# Titan_v1p4.net
KiCad netlist of a schematic drawn in EAGLE
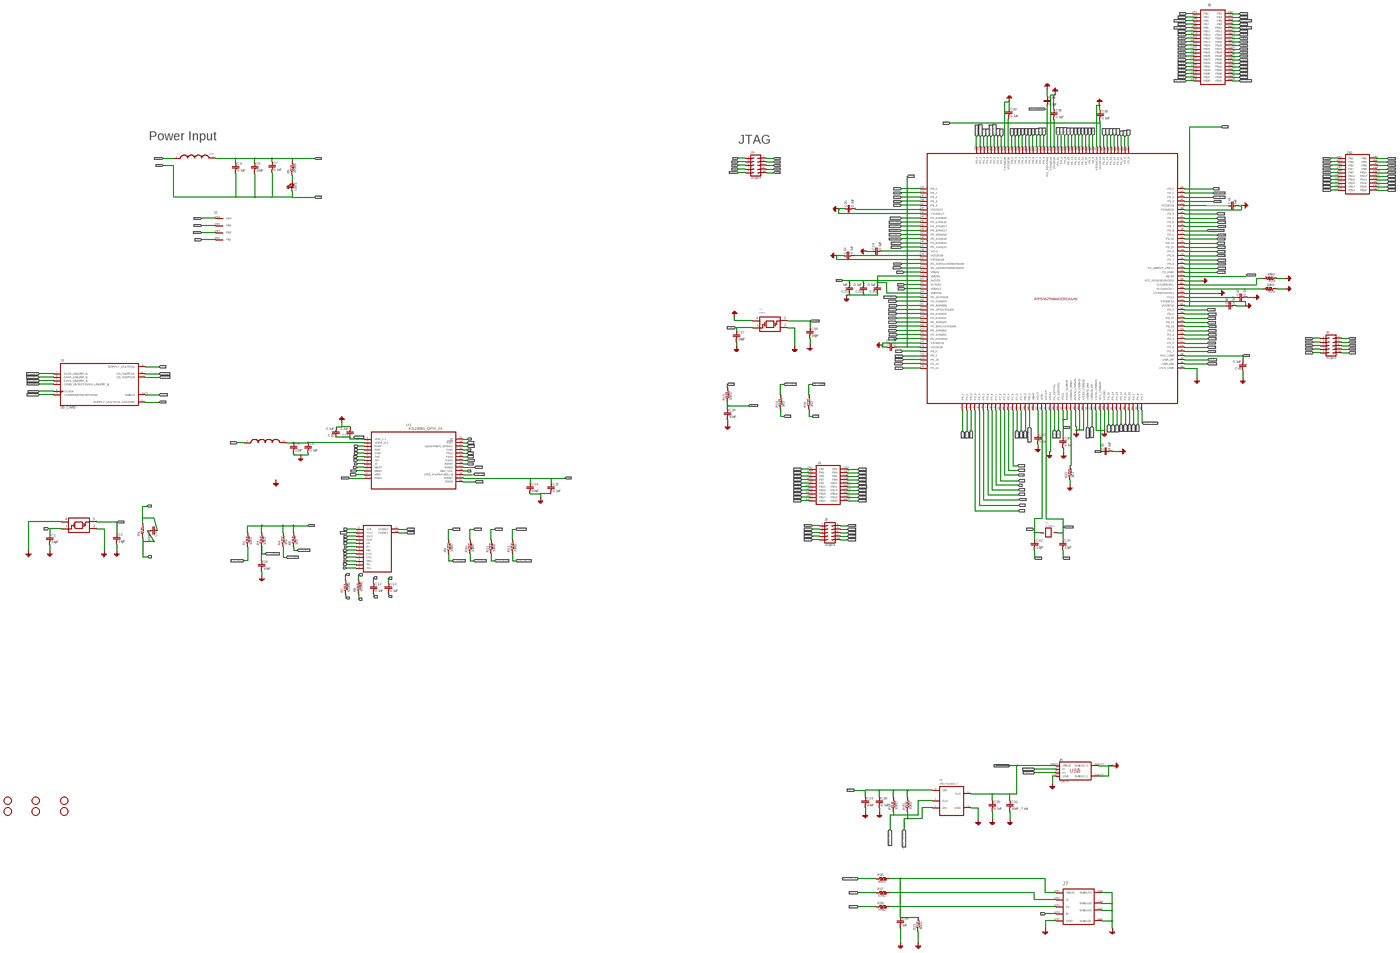
[diagram p0: schematic, sheet 1, overview]
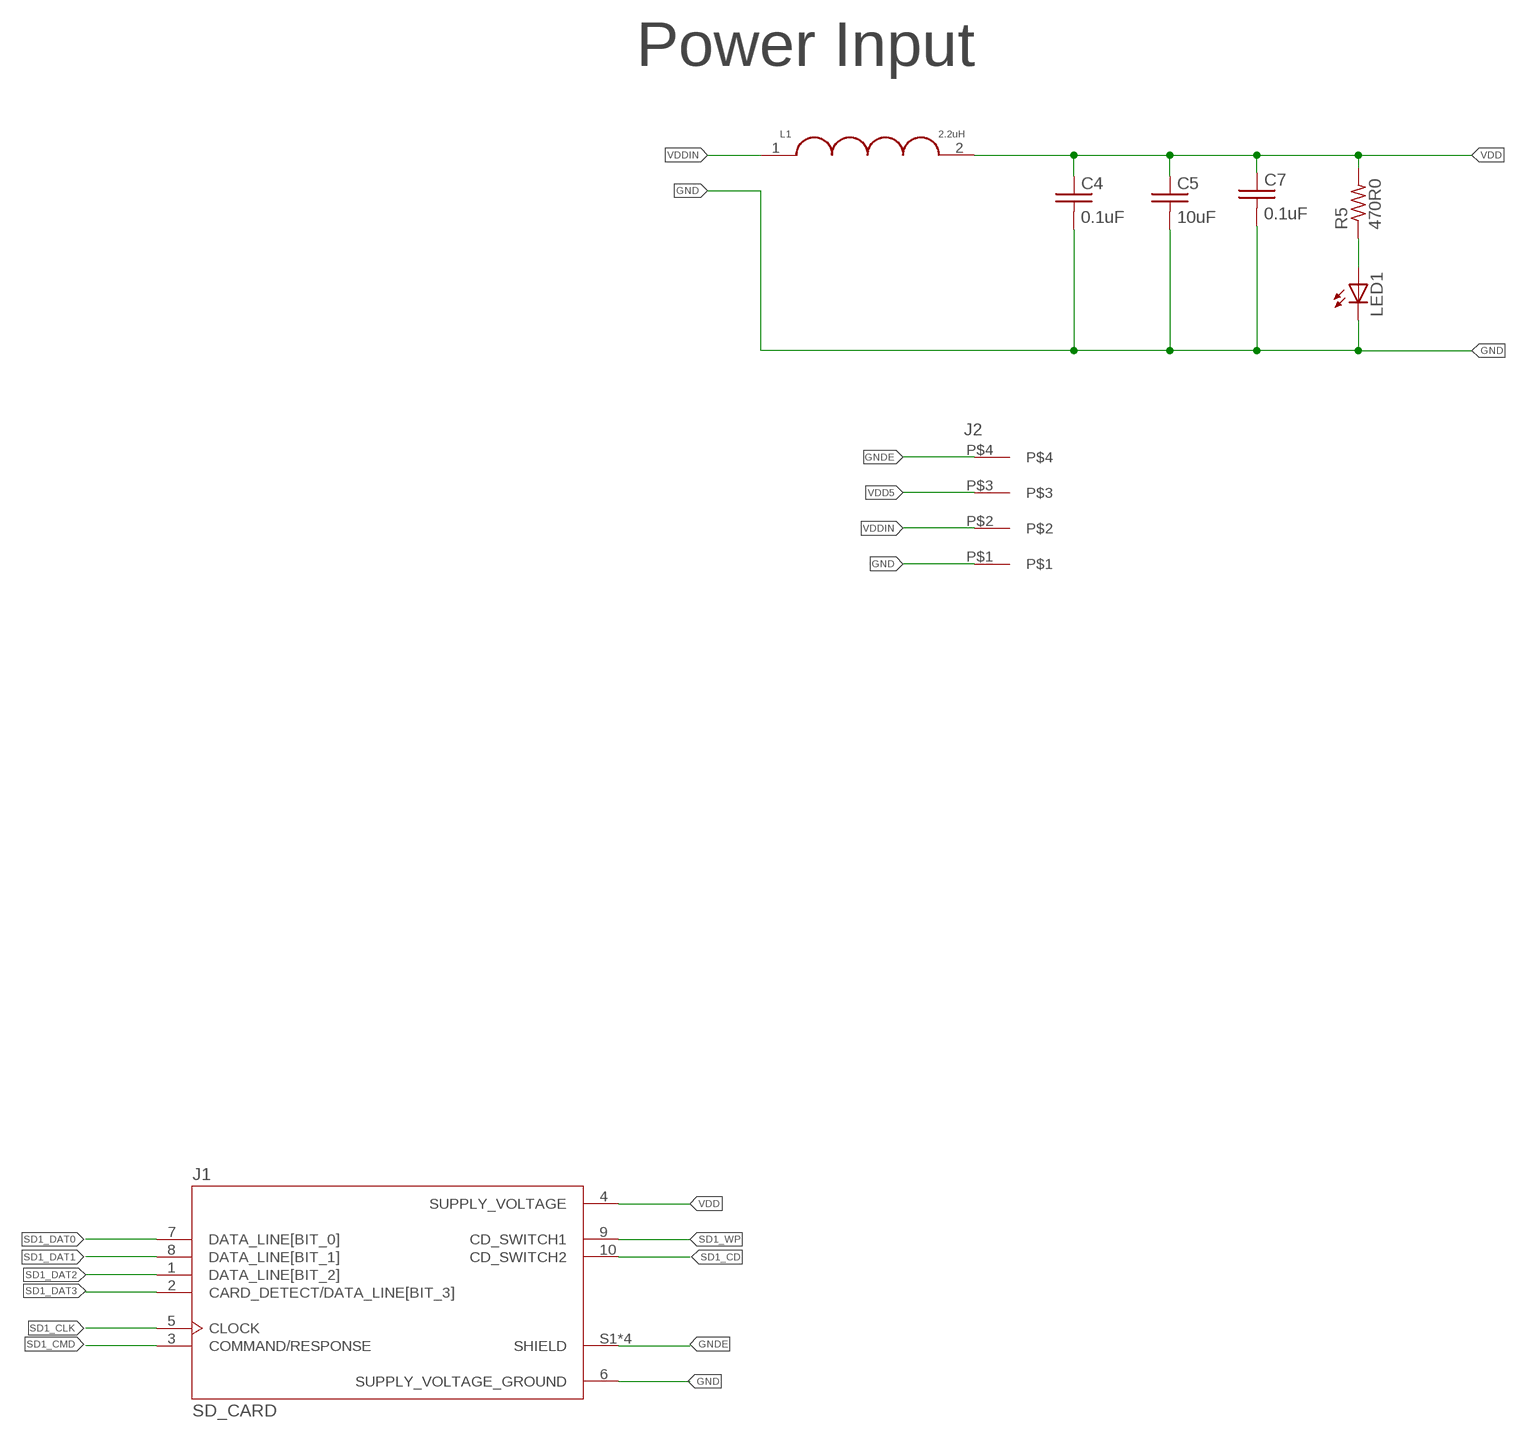
[diagram p1: schematic, sheet 1, part 1 of 5]
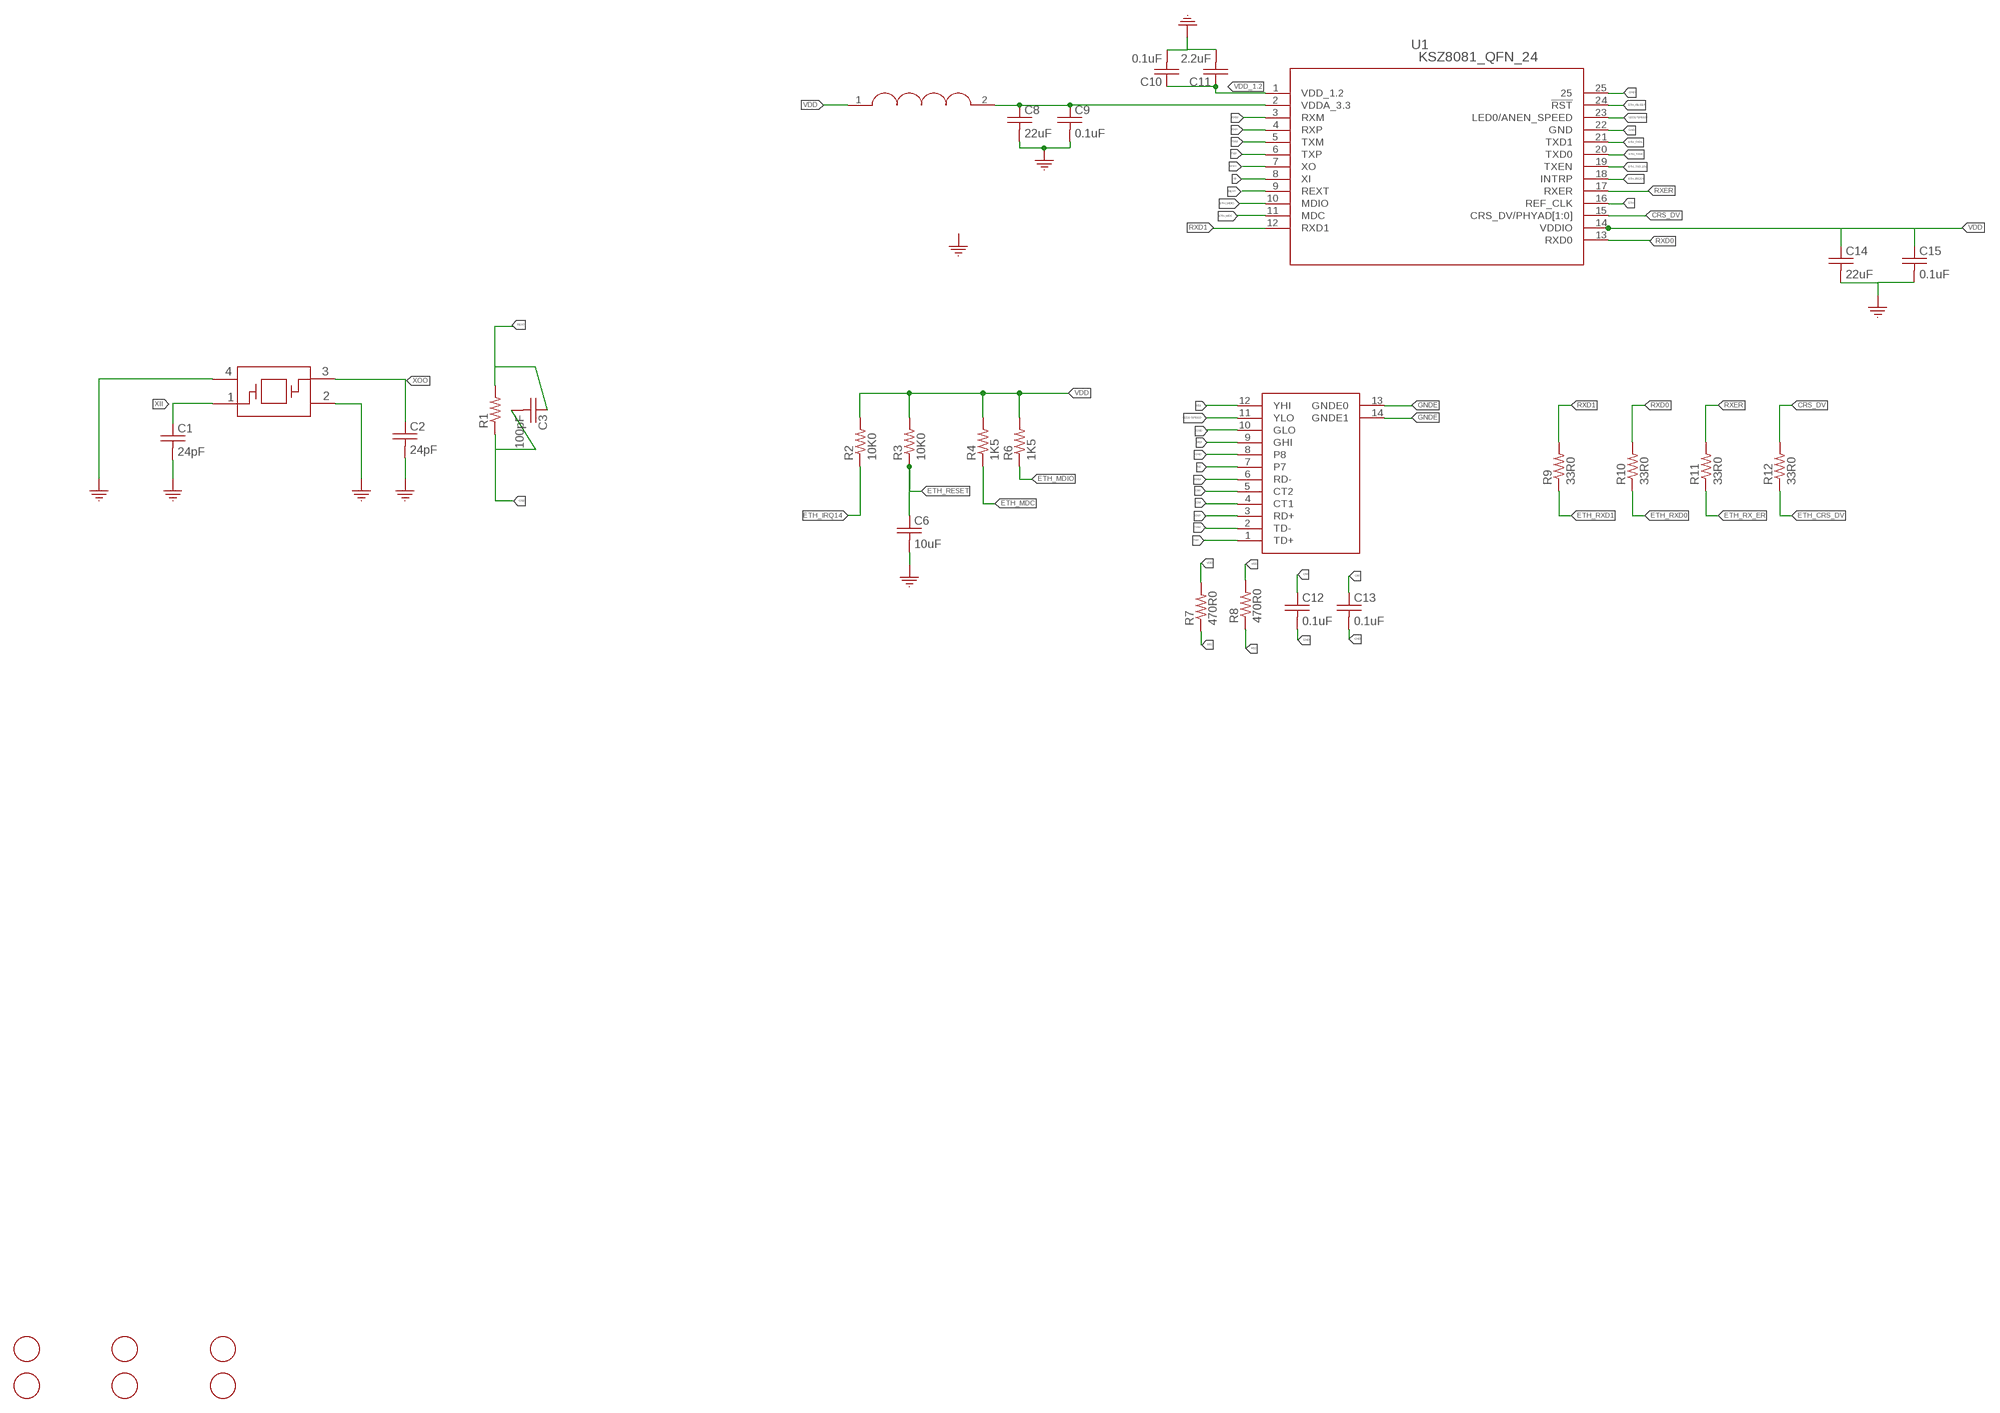
[diagram p2: schematic, sheet 1, part 2 of 5]
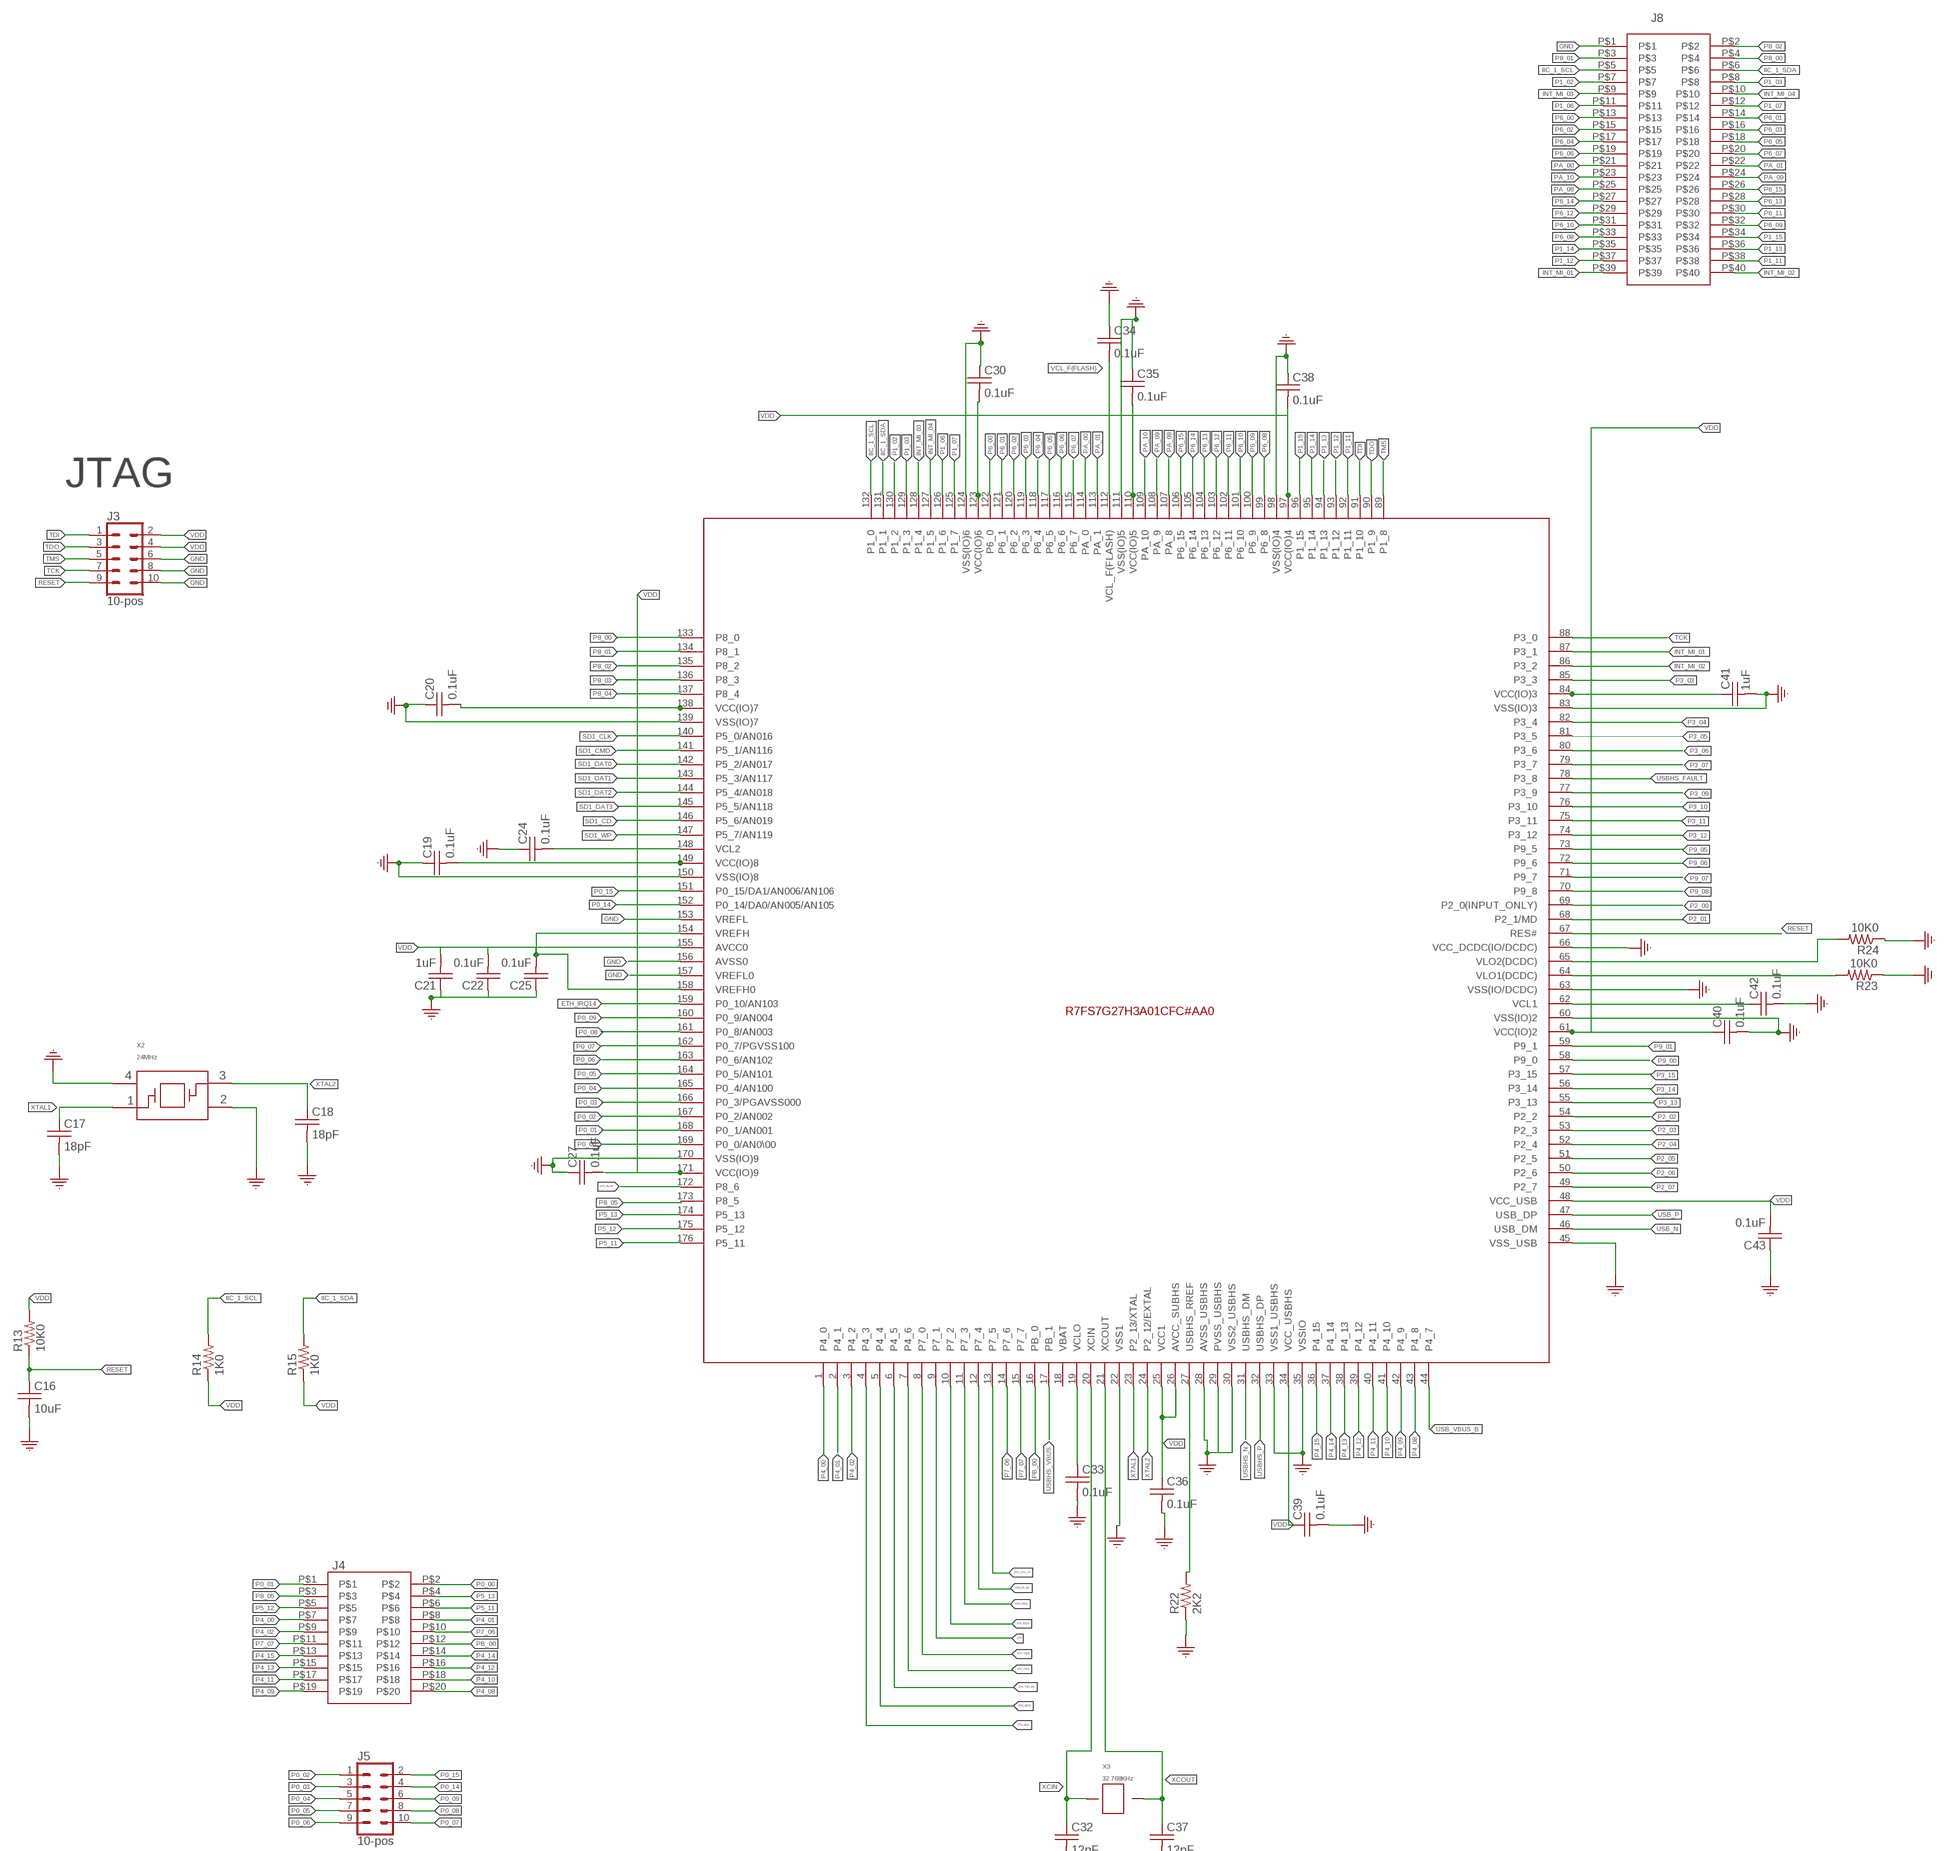
[diagram p3: schematic, sheet 1, part 3 of 5]
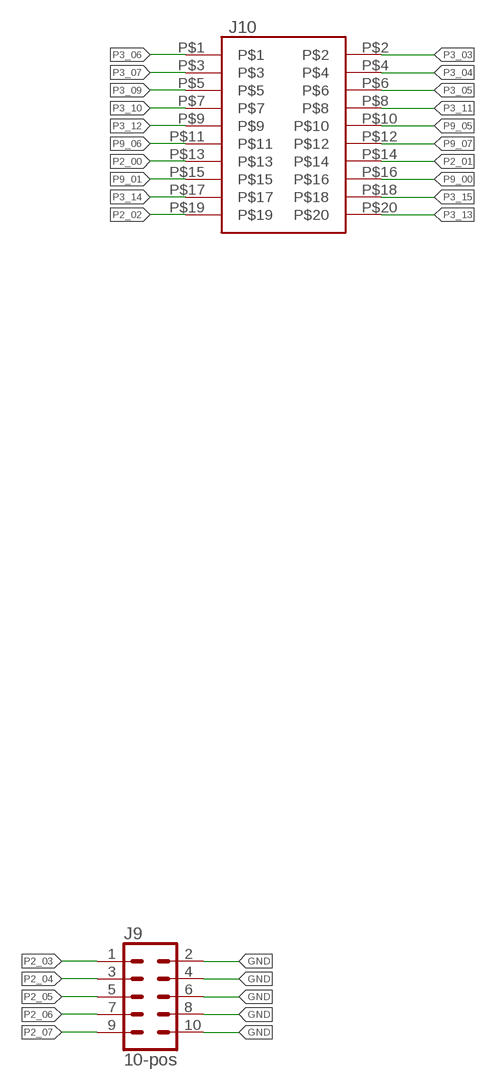
[diagram p4: schematic, sheet 1, part 4 of 5]
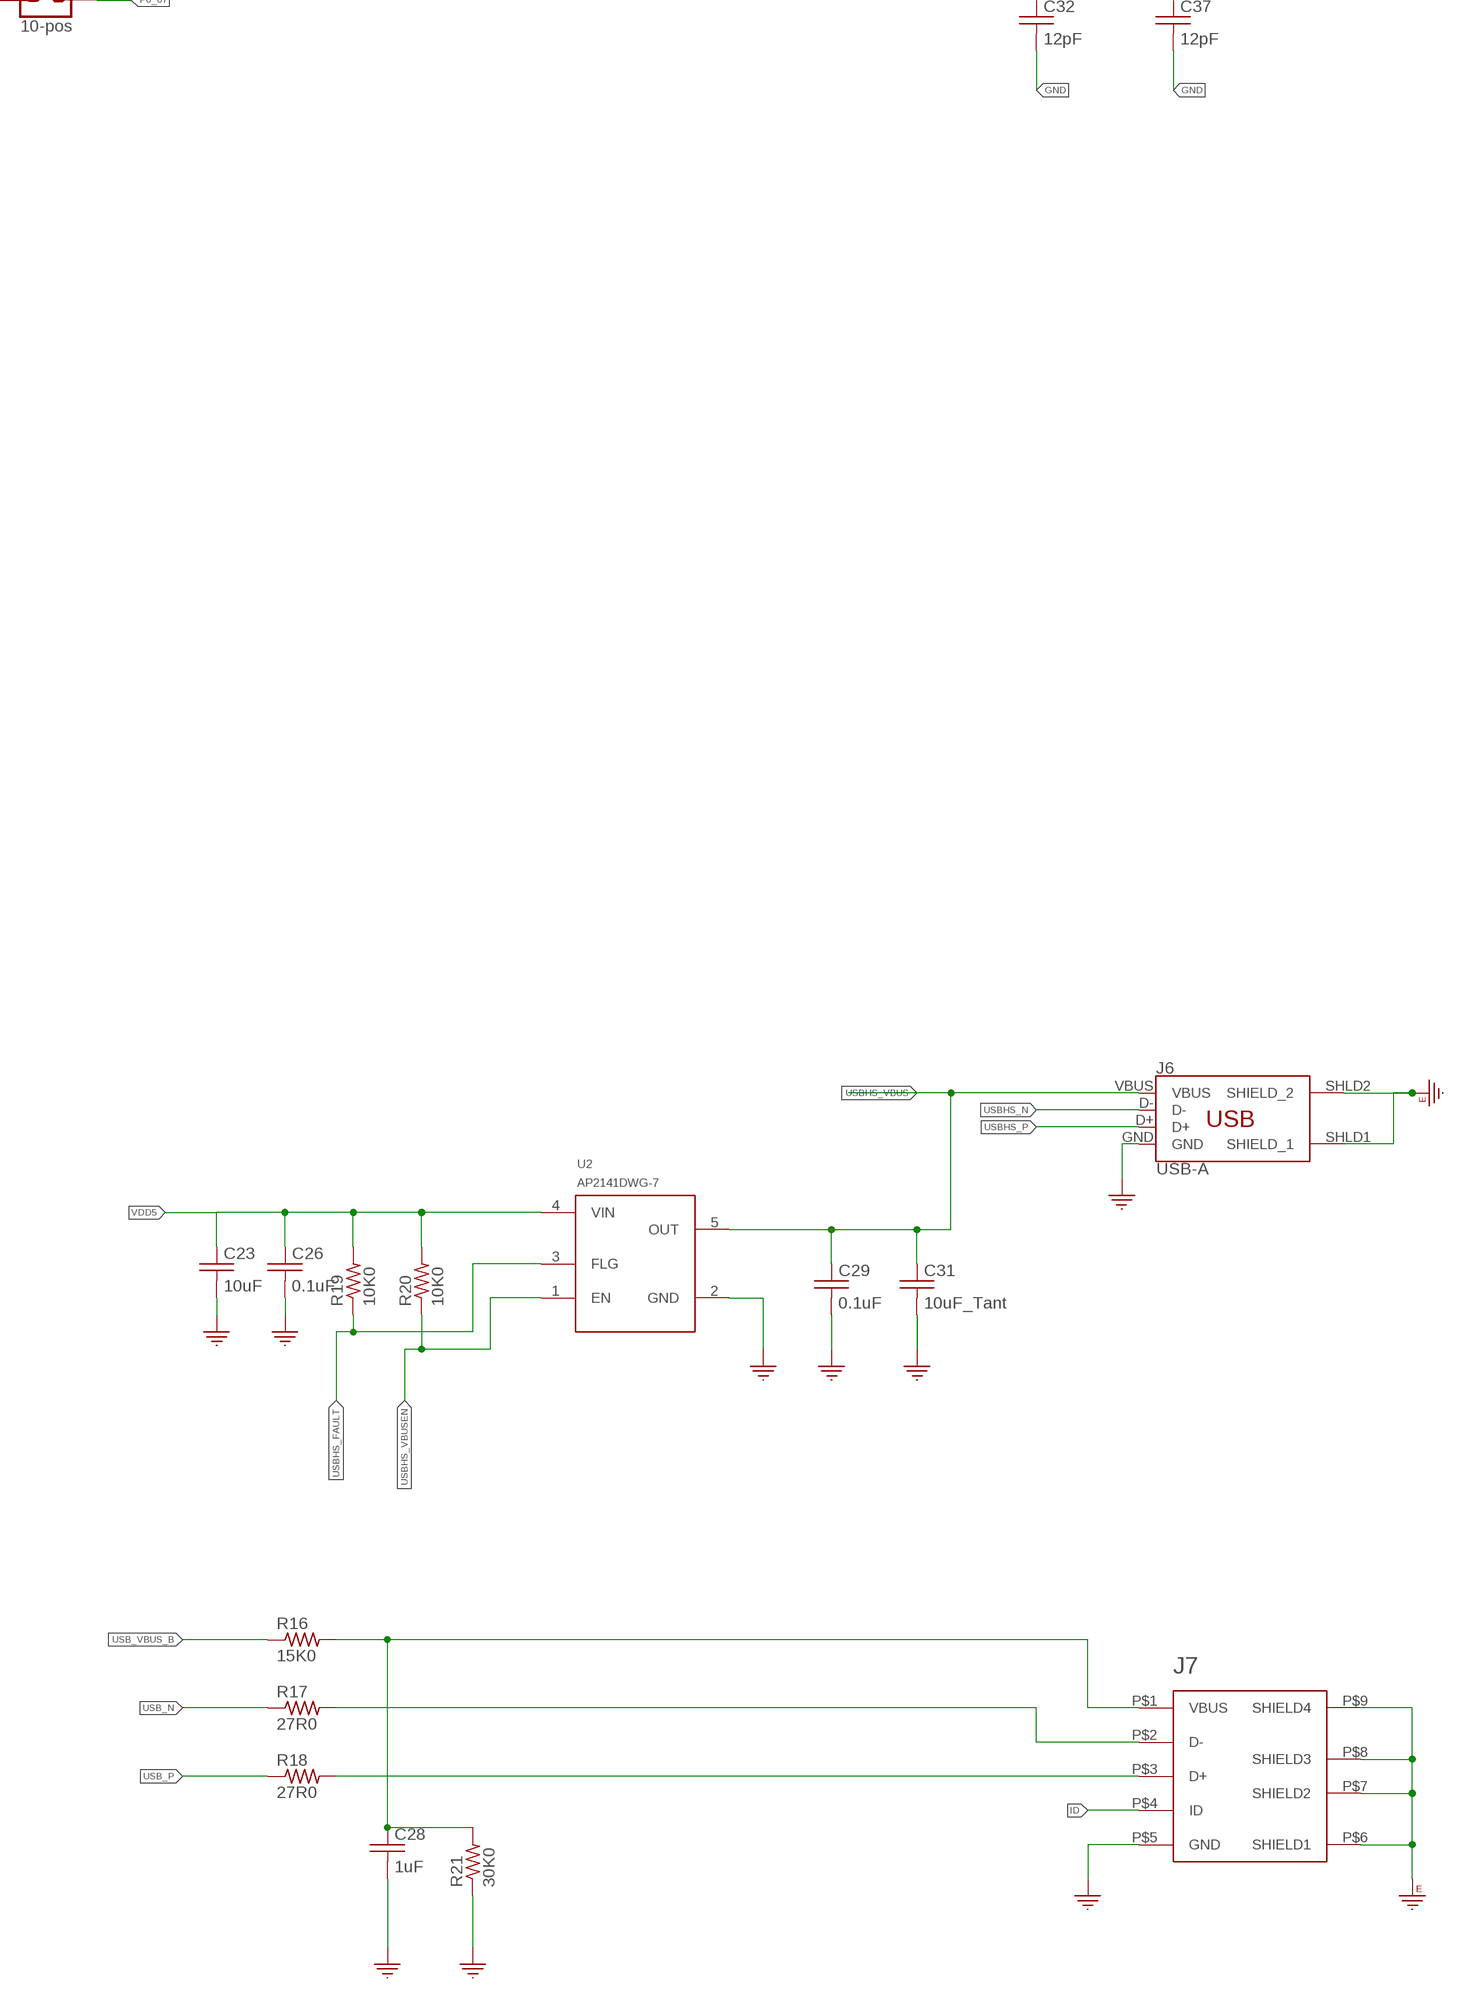
[diagram p5: schematic, sheet 1, part 5 of 5]

(export (version "E")
  (design (tool "Eeschema 10.0.6"))
  (components
    (comp (ref "C1")
      (value "24pF")
      (footprint "eagle-import:0402")
      (fields (field (name "PARTNO") "CC0402GRNPO9BN240"))
      (libsource (lib "eagle-import") (part "C_0402_24PF"))
    )
    (comp (ref "C2")
      (value "24pF")
      (footprint "eagle-import:0402")
      (fields (field (name "PARTNO") "CC0402GRNPO9BN240"))
      (libsource (lib "eagle-import") (part "C_0402_24PF"))
    )
    (comp (ref "C3")
      (value "100pF")
      (footprint "eagle-import:0402")
      (fields (field (name "PARTNO") "CL05C101JB5NNNC"))
      (libsource (lib "eagle-import") (part "C_0402_100PF"))
    )
    (comp (ref "C4")
      (value "0.1uF")
      (footprint "eagle-import:0402")
      (fields (field (name "PARTNO") "CL05F104ZO5NNNC"))
      (libsource (lib "eagle-import") (part "C_0402_0.1UF"))
    )
    (comp (ref "C5")
      (value "10uF")
      (footprint "eagle-import:0402")
      (fields (field (name "PARTNO") "CL05A106MP8NUB8"))
      (libsource (lib "eagle-import") (part "C_0402_10UF"))
    )
    (comp (ref "C6")
      (value "10uF")
      (footprint "eagle-import:0402")
      (fields (field (name "PARTNO") "CL05A106MP8NUB8"))
      (libsource (lib "eagle-import") (part "C_0402_10UF"))
    )
    (comp (ref "C7")
      (value "0.1uF")
      (footprint "eagle-import:0402")
      (fields (field (name "PARTNO") "CL05F104ZO5NNNC"))
      (libsource (lib "eagle-import") (part "C_0402_0.1UF"))
    )
    (comp (ref "C8")
      (value "22uF")
      (footprint "eagle-import:0402")
      (fields (field (name "PARTNO") "CL05A226MQ5N6J8"))
      (libsource (lib "eagle-import") (part "C_0402_22UF"))
    )
    (comp (ref "C9")
      (value "0.1uF")
      (footprint "eagle-import:0402")
      (fields (field (name "PARTNO") "CL05F104ZO5NNNC"))
      (libsource (lib "eagle-import") (part "C_0402_0.1UF"))
    )
    (comp (ref "C10")
      (value "0.1uF")
      (footprint "eagle-import:0402")
      (fields (field (name "PARTNO") "CL05F104ZO5NNNC"))
      (libsource (lib "eagle-import") (part "C_0402_0.1UF"))
    )
    (comp (ref "C11")
      (value "2.2uF")
      (footprint "eagle-import:0402")
      (fields (field (name "PARTNO") "GRM155C81C225ME15D"))
      (libsource (lib "eagle-import") (part "C_0402_2.2UF"))
    )
    (comp (ref "C12")
      (value "0.1uF")
      (footprint "eagle-import:0402")
      (fields (field (name "PARTNO") "CL05F104ZO5NNNC"))
      (libsource (lib "eagle-import") (part "C_0402_0.1UF"))
    )
    (comp (ref "C13")
      (value "0.1uF")
      (footprint "eagle-import:0402")
      (fields (field (name "PARTNO") "CL05F104ZO5NNNC"))
      (libsource (lib "eagle-import") (part "C_0402_0.1UF"))
    )
    (comp (ref "C14")
      (value "22uF")
      (footprint "eagle-import:0402")
      (fields (field (name "PARTNO") "CL05A226MQ5N6J8"))
      (libsource (lib "eagle-import") (part "C_0402_22UF"))
    )
    (comp (ref "C15")
      (value "0.1uF")
      (footprint "eagle-import:0402")
      (fields (field (name "PARTNO") "CL05F104ZO5NNNC"))
      (libsource (lib "eagle-import") (part "C_0402_0.1UF"))
    )
    (comp (ref "C16")
      (value "10uF")
      (footprint "eagle-import:0402")
      (fields (field (name "PARTNO") "CL05A106MP8NUB8"))
      (libsource (lib "eagle-import") (part "C_0402_10UF"))
    )
    (comp (ref "C17")
      (value "18pF")
      (footprint "eagle-import:0402")
      (fields (field (name "PARTNO") "UMK105CG180JV-F"))
      (libsource (lib "eagle-import") (part "C_0402_18PF"))
    )
    (comp (ref "C18")
      (value "18pF")
      (footprint "eagle-import:0402")
      (fields (field (name "PARTNO") "UMK105CG180JV-F"))
      (libsource (lib "eagle-import") (part "C_0402_18PF"))
    )
    (comp (ref "C19")
      (value "0.1uF")
      (footprint "eagle-import:0402")
      (fields (field (name "PARTNO") "CL05F104ZO5NNNC"))
      (libsource (lib "eagle-import") (part "C_0402_0.1UF"))
    )
    (comp (ref "C20")
      (value "0.1uF")
      (footprint "eagle-import:0402")
      (fields (field (name "PARTNO") "CL05F104ZO5NNNC"))
      (libsource (lib "eagle-import") (part "C_0402_0.1UF"))
    )
    (comp (ref "C21")
      (value "1uF")
      (footprint "eagle-import:0402")
      (fields (field (name "PARTNO") "CL05A105KO5NNNC"))
      (libsource (lib "eagle-import") (part "C_0402_1UF"))
    )
    (comp (ref "C22")
      (value "0.1uF")
      (footprint "eagle-import:0402")
      (fields (field (name "PARTNO") "CL05F104ZO5NNNC"))
      (libsource (lib "eagle-import") (part "C_0402_0.1UF"))
    )
    (comp (ref "C23")
      (value "10uF")
      (footprint "eagle-import:0402")
      (fields (field (name "PARTNO") "CL05A106MP8NUB8"))
      (libsource (lib "eagle-import") (part "C_0402_10UF"))
    )
    (comp (ref "C24")
      (value "0.1uF")
      (footprint "eagle-import:0402")
      (fields (field (name "PARTNO") "CL05F104ZO5NNNC"))
      (libsource (lib "eagle-import") (part "C_0402_0.1UF"))
    )
    (comp (ref "C25")
      (value "0.1uF")
      (footprint "eagle-import:0402")
      (fields (field (name "PARTNO") "CL05F104ZO5NNNC"))
      (libsource (lib "eagle-import") (part "C_0402_0.1UF"))
    )
    (comp (ref "C26")
      (value "0.1uF")
      (footprint "eagle-import:0402")
      (fields (field (name "PARTNO") "CL05F104ZO5NNNC"))
      (libsource (lib "eagle-import") (part "C_0402_0.1UF"))
    )
    (comp (ref "C27")
      (value "0.1uF")
      (footprint "eagle-import:0402")
      (fields (field (name "PARTNO") "CL05F104ZO5NNNC"))
      (libsource (lib "eagle-import") (part "C_0402_0.1UF"))
    )
    (comp (ref "C28")
      (value "1uF")
      (footprint "eagle-import:0402")
      (fields (field (name "PARTNO") "CL05A105KO5NNNC"))
      (libsource (lib "eagle-import") (part "C_0402_1UF"))
    )
    (comp (ref "C29")
      (value "0.1uF")
      (footprint "eagle-import:0402")
      (fields (field (name "PARTNO") "CL05F104ZO5NNNC"))
      (libsource (lib "eagle-import") (part "C_0402_0.1UF"))
    )
    (comp (ref "C30")
      (value "0.1uF")
      (footprint "eagle-import:0402")
      (fields (field (name "PARTNO") "CL05F104ZO5NNNC"))
      (libsource (lib "eagle-import") (part "C_0402_0.1UF"))
    )
    (comp (ref "C31")
      (value "10uF_Tant")
      (footprint "eagle-import:C1210")
      (fields (field (name "PARTNO") "TPST106K016H0800"))
      (libsource (lib "eagle-import") (part "C_1210_10UF_TANT"))
    )
    (comp (ref "C32")
      (value "12pF")
      (footprint "eagle-import:0402")
      (fields (field (name "PARTNO") "CL05C120JB5NNNC"))
      (libsource (lib "eagle-import") (part "C_0402_12PF"))
    )
    (comp (ref "C33")
      (value "0.1uF")
      (footprint "eagle-import:0402")
      (fields (field (name "PARTNO") "CL05F104ZO5NNNC"))
      (libsource (lib "eagle-import") (part "C_0402_0.1UF"))
    )
    (comp (ref "C34")
      (value "0.1uF")
      (footprint "eagle-import:0402")
      (fields (field (name "PARTNO") "CL05F104ZO5NNNC"))
      (libsource (lib "eagle-import") (part "C_0402_0.1UF"))
    )
    (comp (ref "C35")
      (value "0.1uF")
      (footprint "eagle-import:0402")
      (fields (field (name "PARTNO") "CL05F104ZO5NNNC"))
      (libsource (lib "eagle-import") (part "C_0402_0.1UF"))
    )
    (comp (ref "C36")
      (value "0.1uF")
      (footprint "eagle-import:0402")
      (fields (field (name "PARTNO") "CL05F104ZO5NNNC"))
      (libsource (lib "eagle-import") (part "C_0402_0.1UF"))
    )
    (comp (ref "C37")
      (value "12pF")
      (footprint "eagle-import:0402")
      (fields (field (name "PARTNO") "CL05C120JB5NNNC"))
      (libsource (lib "eagle-import") (part "C_0402_12PF"))
    )
    (comp (ref "C38")
      (value "0.1uF")
      (footprint "eagle-import:0402")
      (fields (field (name "PARTNO") "CL05F104ZO5NNNC"))
      (libsource (lib "eagle-import") (part "C_0402_0.1UF"))
    )
    (comp (ref "C39")
      (value "0.1uF")
      (footprint "eagle-import:0402")
      (fields (field (name "PARTNO") "CL05F104ZO5NNNC"))
      (libsource (lib "eagle-import") (part "C_0402_0.1UF"))
    )
    (comp (ref "C40")
      (value "0.1uF")
      (footprint "eagle-import:0402")
      (fields (field (name "PARTNO") "CL05F104ZO5NNNC"))
      (libsource (lib "eagle-import") (part "C_0402_0.1UF"))
    )
    (comp (ref "C41")
      (value "1uF")
      (footprint "eagle-import:0402")
      (fields (field (name "PARTNO") "CL05A105KO5NNNC"))
      (libsource (lib "eagle-import") (part "C_0402_1UF"))
    )
    (comp (ref "C42")
      (value "0.1uF")
      (footprint "eagle-import:0402")
      (fields (field (name "PARTNO") "CL05F104ZO5NNNC"))
      (libsource (lib "eagle-import") (part "C_0402_0.1UF"))
    )
    (comp (ref "C43")
      (value "0.1uF")
      (footprint "eagle-import:0402")
      (fields (field (name "PARTNO") "CL05F104ZO5NNNC"))
      (libsource (lib "eagle-import") (part "C_0402_0.1UF"))
    )
    (comp (ref "FB1")
      (value "FB2_603")
      (footprint "eagle-import:0603")
      (fields (field (name "PARTNO") "BLM18PG121SN1D"))
      (libsource (lib "eagle-import") (part "FB_0603_120_OHM0603"))
    )
    (comp (ref "J1")
      (value "SD_CARD")
      (footprint "eagle-import:SD_CARD")
      (fields (field (name "MF") "Amphenol ICC") (field (name "PARTNO") "114-00841-68"))
      (libsource (lib "eagle-import") (part "SD_CARD_1140084168"))
    )
    (comp (ref "J2")
      (value "4-pos")
      (footprint "eagle-import:1X4_3.81MM_PITCH")
      (fields (field (name "PARTNO") "691322310004"))
      (libsource (lib "eagle-import") (part "3.81MM_1_X_4_RT_ANGLE_PLUG_HEADER"))
    )
    (comp (ref "J3")
      (value "10-pos")
      (footprint "eagle-import:2X5")
      (fields (field (name "PARTNO") "PH2RA-10-UA"))
      (libsource (lib "eagle-import") (part "CONN_05X2_RAPTH"))
    )
    (comp (ref "J4")
      (value "20-pos")
      (footprint "eagle-import:2_X_10_.1_INCH")
      (fields (field (name "PARTNO") "67996-420HLF"))
      (libsource (lib "eagle-import") (part "2_X_10_HEADER_GENERIC"))
    )
    (comp (ref "J5")
      (value "10-pos")
      (footprint "eagle-import:2X5")
      (fields (field (name "PARTNO") "PH2RA-10-UA"))
      (libsource (lib "eagle-import") (part "CONN_05X2_RAPTH"))
    )
    (comp (ref "J6")
      (value "USB-A")
      (footprint "eagle-import:USB_A_SMT")
      (fields (field (name "PARTNO") "87583-3010RPALF"))
      (libsource (lib "eagle-import") (part "USB_A"))
    )
    (comp (ref "J7")
      (value "USB-B-Micro")
      (footprint "eagle-import:USB_MICRO-B")
      (fields (field (name "PARTNO") "10118192-0002LF"))
      (libsource (lib "eagle-import") (part "USB_MICRO-B"))
    )
    (comp (ref "J8")
      (value "40-pos")
      (footprint "eagle-import:HEADER_2_X_20_.1_INCH")
      (fields (field (name "PARTNO") "61304021021"))
      (libsource (lib "eagle-import") (part "HEADER_2_X_20_GENERIC"))
    )
    (comp (ref "J9")
      (value "10-pos")
      (footprint "eagle-import:2X5")
      (fields (field (name "PARTNO") "PH2RA-10-UA"))
      (libsource (lib "eagle-import") (part "CONN_05X2_RAPTH"))
    )
    (comp (ref "J10")
      (value "20-pos")
      (footprint "eagle-import:2_X_10_.1_INCH")
      (fields (field (name "PARTNO") "67996-420HLF"))
      (libsource (lib "eagle-import") (part "2_X_10_HEADER_GENERIC"))
    )
    (comp (ref "L1")
      (value "2.2uH")
      (footprint "eagle-import:1008")
      (fields (field (name "PARTNO") "LQM2HPN2R2MG0L"))
      (libsource (lib "eagle-import") (part "INDUCTOR_1008_2.2_MH_1.3A"))
    )
    (comp (ref "LED1")
      (value "Green")
      (footprint "eagle-import:0805")
      (fields (field (name "PARTNO") "LG R971-KN-1"))
      (libsource (lib "eagle-import") (part "LED_0805_GREEN"))
    )
    (comp (ref "R1")
      (value "6K49")
      (footprint "eagle-import:0402")
      (fields (field (name "PARTNO") "RMCF0402FT6K49"))
      (libsource (lib "eagle-import") (part "R_0402_6K49"))
    )
    (comp (ref "R2")
      (value "10K0")
      (footprint "eagle-import:0402")
      (fields (field (name "PARTNO") "RMCF0402JT10K0"))
      (libsource (lib "eagle-import") (part "R_0402_10K0"))
    )
    (comp (ref "R3")
      (value "10K0")
      (footprint "eagle-import:0402")
      (fields (field (name "PARTNO") "RMCF0402JT10K0"))
      (libsource (lib "eagle-import") (part "R_0402_10K0"))
    )
    (comp (ref "R4")
      (value "1K5")
      (footprint "eagle-import:0402")
      (fields (field (name "PARTNO") "RMCF0402JT1K50"))
      (libsource (lib "eagle-import") (part "R_0402_1K5"))
    )
    (comp (ref "R5")
      (value "470R0")
      (footprint "eagle-import:0402")
      (fields (field (name "PARTNO") "RMCF0402JT470R"))
      (libsource (lib "eagle-import") (part "R_0402_470R0"))
    )
    (comp (ref "R6")
      (value "1K5")
      (footprint "eagle-import:0402")
      (fields (field (name "PARTNO") "RMCF0402JT1K50"))
      (libsource (lib "eagle-import") (part "R_0402_1K5"))
    )
    (comp (ref "R7")
      (value "470R0")
      (footprint "eagle-import:0402")
      (fields (field (name "PARTNO") "RMCF0402JT470R"))
      (libsource (lib "eagle-import") (part "R_0402_470R0"))
    )
    (comp (ref "R8")
      (value "470R0")
      (footprint "eagle-import:0402")
      (fields (field (name "PARTNO") "RMCF0402JT470R"))
      (libsource (lib "eagle-import") (part "R_0402_470R0"))
    )
    (comp (ref "R9")
      (value "33R0")
      (footprint "eagle-import:0402")
      (fields (field (name "PARTNO") "RMCF0402JT33R0"))
      (libsource (lib "eagle-import") (part "R_0402_33R0"))
    )
    (comp (ref "R10")
      (value "33R0")
      (footprint "eagle-import:0402")
      (fields (field (name "PARTNO") "RMCF0402JT33R0"))
      (libsource (lib "eagle-import") (part "R_0402_33R0"))
    )
    (comp (ref "R11")
      (value "33R0")
      (footprint "eagle-import:0402")
      (fields (field (name "PARTNO") "RMCF0402JT33R0"))
      (libsource (lib "eagle-import") (part "R_0402_33R0"))
    )
    (comp (ref "R12")
      (value "33R0")
      (footprint "eagle-import:0402")
      (fields (field (name "PARTNO") "RMCF0402JT33R0"))
      (libsource (lib "eagle-import") (part "R_0402_33R0"))
    )
    (comp (ref "R13")
      (value "10K0")
      (footprint "eagle-import:0402")
      (fields (field (name "PARTNO") "RMCF0402JT10K0"))
      (libsource (lib "eagle-import") (part "R_0402_10K0"))
    )
    (comp (ref "R14")
      (value "1K0")
      (footprint "eagle-import:0402")
      (fields (field (name "PARTNO") "CRG0402J1K0"))
      (libsource (lib "eagle-import") (part "R_0402_1K0"))
    )
    (comp (ref "R15")
      (value "1K0")
      (footprint "eagle-import:0402")
      (fields (field (name "PARTNO") "CRG0402J1K0"))
      (libsource (lib "eagle-import") (part "R_0402_1K0"))
    )
    (comp (ref "R16")
      (value "15K0")
      (footprint "eagle-import:0402")
      (fields (field (name "PARTNO") "RMCF0402JT15K0"))
      (libsource (lib "eagle-import") (part "R_0402_15K0"))
    )
    (comp (ref "R17")
      (value "27R0")
      (footprint "eagle-import:0402")
      (fields (field (name "PARTNO") "RMCF0402JT27R0"))
      (libsource (lib "eagle-import") (part "R_0402_27R0"))
    )
    (comp (ref "R18")
      (value "27R0")
      (footprint "eagle-import:0402")
      (fields (field (name "PARTNO") "RMCF0402JT27R0"))
      (libsource (lib "eagle-import") (part "R_0402_27R0"))
    )
    (comp (ref "R19")
      (value "10K0")
      (footprint "eagle-import:0402")
      (fields (field (name "PARTNO") "RMCF0402JT10K0"))
      (libsource (lib "eagle-import") (part "R_0402_10K0"))
    )
    (comp (ref "R20")
      (value "10K0")
      (footprint "eagle-import:0402")
      (fields (field (name "PARTNO") "RMCF0402JT10K0"))
      (libsource (lib "eagle-import") (part "R_0402_10K0"))
    )
    (comp (ref "R21")
      (value "30K0")
      (footprint "eagle-import:0402")
      (fields (field (name "PARTNO") "RC0402JR-0730KL"))
      (libsource (lib "eagle-import") (part "R_0402_30K0"))
    )
    (comp (ref "R22")
      (value "2K2")
      (footprint "eagle-import:0402")
      (fields (field (name "PARTNO") "RMCF0402JT2K20"))
      (libsource (lib "eagle-import") (part "R_0402_2K2"))
    )
    (comp (ref "R23")
      (value "10K0")
      (footprint "eagle-import:0402")
      (fields (field (name "PARTNO") "RMCF0402JT10K0"))
      (libsource (lib "eagle-import") (part "R_0402_10K0"))
    )
    (comp (ref "R24")
      (value "10K0")
      (footprint "eagle-import:0402")
      (fields (field (name "PARTNO") "RMCF0402JT10K0"))
      (libsource (lib "eagle-import") (part "R_0402_10K0"))
    )
    (comp (ref "RJ1")
      (value "RJ45")
      (footprint "eagle-import:RJ45_TH_ELEC")
      (fields (field (name "PARTNO") "13F-64GYD2PL2NL"))
      (libsource (lib "eagle-import") (part "RJ45_WITH_ELEC"))
    )
    (comp (ref "U$1")
      (value "FIDUCIAL_1MM")
      (footprint "eagle-import:FIDUCIAL_1MM")
      (libsource (lib "eagle-import") (part "FIDUCIAL_1MM"))
    )
    (comp (ref "U$2")
      (value "FIDUCIAL_1MM")
      (footprint "eagle-import:FIDUCIAL_1MM")
      (libsource (lib "eagle-import") (part "FIDUCIAL_1MM"))
    )
    (comp (ref "U$3")
      (value "FIDUCIAL_1MM")
      (footprint "eagle-import:FIDUCIAL_1MM")
      (libsource (lib "eagle-import") (part "FIDUCIAL_1MM"))
    )
    (comp (ref "U$4")
      (value "FIDUCIAL_1MM")
      (footprint "eagle-import:FIDUCIAL_1MM")
      (libsource (lib "eagle-import") (part "FIDUCIAL_1MM"))
    )
    (comp (ref "U$5")
      (value "FIDUCIAL_1MM")
      (footprint "eagle-import:FIDUCIAL_1MM")
      (libsource (lib "eagle-import") (part "FIDUCIAL_1MM"))
    )
    (comp (ref "U$6")
      (value "FIDUCIAL_1MM")
      (footprint "eagle-import:FIDUCIAL_1MM")
      (libsource (lib "eagle-import") (part "FIDUCIAL_1MM"))
    )
    (comp (ref "U1")
      (value "KSZ8081_QFN_24")
      (footprint "eagle-import:QFN-24-M")
      (fields (field (name "PARTNO") "KSZ8081RNACA"))
      (libsource (lib "eagle-import") (part "KSZ8081RNACAQFN-24-M"))
    )
    (comp (ref "U2")
      (value "AP2151DWG-7")
      (footprint "eagle-import:SOT-23-5")
      (fields (field (name "PARTNO") "AP2151WG-7"))
      (libsource (lib "eagle-import") (part "AP2151DWG-7"))
    )
    (comp (ref "U3")
      (value "S7G2LQFP176")
      (footprint "eagle-import:LQFP176_24X24")
      (fields (field (name "PARTNO") "R7FS7G27H3A01CFC#AA0"))
      (libsource (lib "eagle-import") (part "RENESAS_S7G2_X_176"))
    )
    (comp (ref "X1")
      (value "25MHz")
      (footprint "eagle-import:SMD_3225")
      (fields (field (name "PARTNO") "FA-238 25.0000MB-B3"))
      (libsource (lib "eagle-import") (part "XTAL_25_MHZ"))
    )
    (comp (ref "X2")
      (value "24MHz")
      (footprint "eagle-import:SMD_3225")
      (fields (field (name "PARTNO") "FA-238 24.0000MB-C3 "))
      (libsource (lib "eagle-import") (part "XTAL_24_MHZ"))
    )
    (comp (ref "X3")
      (value "32.768KHz")
      (footprint "eagle-import:SMD_X_2_PADS")
      (fields (field (name "PARTNO") "ABS07-32.768KHZ-T"))
      (libsource (lib "eagle-import") (part "XTAL_32.768KHZ"))
    )
  )
  (nets
    (net (code "1") (name "C58") (class "Default")
      (node (ref "C12") (pin "P$1") (pinfunction "1_P$1") (pintype "passive"))
      (node (ref "RJ1") (pin "4") (pinfunction "CT1_4") (pintype "bidirectional"))
    )
    (net (code "2") (name "C60") (class "Default")
      (node (ref "C13") (pin "P$1") (pinfunction "1_P$1") (pintype "passive"))
      (node (ref "RJ1") (pin "5") (pinfunction "CT2_5") (pintype "bidirectional"))
    )
    (net (code "3") (name "CRS_DV") (class "Default")
      (node (ref "R12") (pin "P$2") (pinfunction "2_P$2") (pintype "passive"))
      (node (ref "U1") (pin "15") (pinfunction "CRS_DV/PHYAD[1:0]_15") (pintype "bidirectional"))
    )
    (net (code "4") (name "ETH") (class "Default")
      (node (ref "U1") (pin "16") (pinfunction "REF_CLK_16") (pintype "bidirectional"))
      (node (ref "U3") (pin "9") (pinfunction "P7_1_9") (pintype "bidirectional"))
    )
    (net (code "5") (name "ETH_CRS_DV") (class "Default")
      (node (ref "R12") (pin "P$1") (pinfunction "1_P$1") (pintype "passive"))
      (node (ref "U3") (pin "13") (pinfunction "P7_5_13") (pintype "bidirectional"))
    )
    (net (code "6") (name "ETH_IRQ14") (class "Default")
      (node (ref "R2") (pin "P$1") (pinfunction "1_P$1") (pintype "passive"))
      (node (ref "U1") (pin "18") (pinfunction "INTRP_18") (pintype "bidirectional"))
      (node (ref "U3") (pin "159") (pinfunction "P0_10/AN103_159") (pintype "bidirectional"))
    )
    (net (code "7") (name "ETH_MDC") (class "Default")
      (node (ref "R4") (pin "P$1") (pinfunction "1_P$1") (pintype "passive"))
      (node (ref "U1") (pin "11") (pinfunction "MDC_11") (pintype "input"))
      (node (ref "U3") (pin "4") (pinfunction "P4_3_4") (pintype "bidirectional"))
    )
    (net (code "8") (name "ETH_MDIO") (class "Default")
      (node (ref "R6") (pin "P$1") (pinfunction "1_P$1") (pintype "passive"))
      (node (ref "U1") (pin "10") (pinfunction "MDIO_10") (pintype "bidirectional"))
      (node (ref "U3") (pin "5") (pinfunction "P4_4_5") (pintype "bidirectional"))
    )
    (net (code "9") (name "ETH_RESET") (class "Default")
      (node (ref "C6") (pin "P$1") (pinfunction "1_P$1") (pintype "passive"))
      (node (ref "R3") (pin "P$1") (pinfunction "1_P$1") (pintype "passive"))
      (node (ref "U1") (pin "24") (pinfunction "~{RST}_24") (pintype "input"))
      (node (ref "U3") (pin "172") (pinfunction "P8_6_172") (pintype "bidirectional"))
    )
    (net (code "10") (name "ETH_RXD0") (class "Default")
      (node (ref "R10") (pin "P$1") (pinfunction "1_P$1") (pintype "passive"))
      (node (ref "U3") (pin "10") (pinfunction "P7_2_10") (pintype "bidirectional"))
    )
    (net (code "11") (name "ETH_RXD1") (class "Default")
      (node (ref "R9") (pin "P$1") (pinfunction "1_P$1") (pintype "passive"))
      (node (ref "U3") (pin "11") (pinfunction "P7_3_11") (pintype "bidirectional"))
    )
    (net (code "12") (name "ETH_RX_ER") (class "Default")
      (node (ref "R11") (pin "P$1") (pinfunction "1_P$1") (pintype "passive"))
      (node (ref "U3") (pin "12") (pinfunction "P7_4_12") (pintype "bidirectional"))
    )
    (net (code "13") (name "ETH_TXD0") (class "Default")
      (node (ref "U1") (pin "20") (pinfunction "TXD0_20") (pintype "input"))
      (node (ref "U3") (pin "8") (pinfunction "P7_0_8") (pintype "bidirectional"))
    )
    (net (code "14") (name "ETH_TXD1") (class "Default")
      (node (ref "U1") (pin "21") (pinfunction "TXD1_21") (pintype "bidirectional"))
      (node (ref "U3") (pin "7") (pinfunction "P4_6_7") (pintype "bidirectional"))
    )
    (net (code "15") (name "ETH_TXD_EN") (class "Default")
      (node (ref "U1") (pin "19") (pinfunction "TXEN_19") (pintype "input"))
      (node (ref "U3") (pin "6") (pinfunction "P4_5_6") (pintype "bidirectional"))
    )
    (net (code "16") (name "GND") (class "Default")
      (node (ref "C1") (pin "P$2") (pinfunction "2_P$2") (pintype "passive"))
      (node (ref "C10") (pin "P$2") (pinfunction "2_P$2") (pintype "passive"))
      (node (ref "C11") (pin "P$2") (pinfunction "2_P$2") (pintype "passive"))
      (node (ref "C12") (pin "P$2") (pinfunction "2_P$2") (pintype "passive"))
      (node (ref "C13") (pin "P$2") (pinfunction "2_P$2") (pintype "passive"))
      (node (ref "C14") (pin "P$2") (pinfunction "2_P$2") (pintype "passive"))
      (node (ref "C15") (pin "P$2") (pinfunction "2_P$2") (pintype "passive"))
      (node (ref "C16") (pin "P$2") (pinfunction "2_P$2") (pintype "passive"))
      (node (ref "C17") (pin "P$2") (pinfunction "2_P$2") (pintype "passive"))
      (node (ref "C18") (pin "P$2") (pinfunction "2_P$2") (pintype "passive"))
      (node (ref "C19") (pin "P$1") (pinfunction "1_P$1") (pintype "passive"))
      (node (ref "C2") (pin "P$2") (pinfunction "2_P$2") (pintype "passive"))
      (node (ref "C20") (pin "P$1") (pinfunction "1_P$1") (pintype "passive"))
      (node (ref "C21") (pin "P$1") (pinfunction "1_P$1") (pintype "passive"))
      (node (ref "C22") (pin "P$1") (pinfunction "1_P$1") (pintype "passive"))
      (node (ref "C23") (pin "P$2") (pinfunction "2_P$2") (pintype "passive"))
      (node (ref "C24") (pin "P$1") (pinfunction "1_P$1") (pintype "passive"))
      (node (ref "C25") (pin "P$1") (pinfunction "1_P$1") (pintype "passive"))
      (node (ref "C26") (pin "P$2") (pinfunction "2_P$2") (pintype "passive"))
      (node (ref "C27") (pin "P$1") (pinfunction "1_P$1") (pintype "passive"))
      (node (ref "C28") (pin "P$2") (pinfunction "2_P$2") (pintype "passive"))
      (node (ref "C29") (pin "P$2") (pinfunction "2_P$2") (pintype "passive"))
      (node (ref "C3") (pin "P$2") (pinfunction "2_P$2") (pintype "passive"))
      (node (ref "C30") (pin "P$1") (pinfunction "1_P$1") (pintype "passive"))
      (node (ref "C31") (pin "2") (pinfunction "2_2") (pintype "passive"))
      (node (ref "C32") (pin "P$2") (pinfunction "2_P$2") (pintype "passive"))
      (node (ref "C33") (pin "P$2") (pinfunction "2_P$2") (pintype "passive"))
      (node (ref "C34") (pin "P$1") (pinfunction "1_P$1") (pintype "passive"))
      (node (ref "C35") (pin "P$1") (pinfunction "1_P$1") (pintype "passive"))
      (node (ref "C36") (pin "P$2") (pinfunction "2_P$2") (pintype "passive"))
      (node (ref "C37") (pin "P$2") (pinfunction "2_P$2") (pintype "passive"))
      (node (ref "C38") (pin "P$1") (pinfunction "1_P$1") (pintype "passive"))
      (node (ref "C39") (pin "P$2") (pinfunction "2_P$2") (pintype "passive"))
      (node (ref "C4") (pin "P$2") (pinfunction "2_P$2") (pintype "passive"))
      (node (ref "C40") (pin "P$2") (pinfunction "2_P$2") (pintype "passive"))
      (node (ref "C41") (pin "P$2") (pinfunction "2_P$2") (pintype "passive"))
      (node (ref "C42") (pin "P$2") (pinfunction "2_P$2") (pintype "passive"))
      (node (ref "C43") (pin "P$1") (pinfunction "1_P$1") (pintype "passive"))
      (node (ref "C5") (pin "P$2") (pinfunction "2_P$2") (pintype "passive"))
      (node (ref "C6") (pin "P$2") (pinfunction "2_P$2") (pintype "passive"))
      (node (ref "C7") (pin "P$2") (pinfunction "2_P$2") (pintype "passive"))
      (node (ref "C8") (pin "P$2") (pinfunction "2_P$2") (pintype "passive"))
      (node (ref "C9") (pin "P$2") (pinfunction "2_P$2") (pintype "passive"))
      (node (ref "J1") (pin "6") (pinfunction "SUPPLY_VOLTAGE_GROUND_6") (pintype "power_in"))
      (node (ref "J2") (pin "P$1") (pinfunction "P$1_P$1") (pintype "bidirectional"))
      (node (ref "J3") (pin "10") (pinfunction "10_10") (pintype "passive"))
      (node (ref "J3") (pin "6") (pinfunction "6_6") (pintype "passive"))
      (node (ref "J3") (pin "8") (pinfunction "8_8") (pintype "passive"))
      (node (ref "J6") (pin "GND") (pinfunction "GND_GND") (pintype "power_in"))
      (node (ref "J7") (pin "P$5") (pinfunction "GND_P$5") (pintype "bidirectional"))
      (node (ref "J8") (pin "P$1") (pinfunction "P$1_P$1") (pintype "bidirectional"))
      (node (ref "J9") (pin "10") (pinfunction "10_10") (pintype "passive"))
      (node (ref "J9") (pin "2") (pinfunction "2_2") (pintype "passive"))
      (node (ref "J9") (pin "4") (pinfunction "4_4") (pintype "passive"))
      (node (ref "J9") (pin "6") (pinfunction "6_6") (pintype "passive"))
      (node (ref "J9") (pin "8") (pinfunction "8_8") (pintype "passive"))
      (node (ref "LED1") (pin "2") (pinfunction "C_2") (pintype "passive"))
      (node (ref "R1") (pin "P$1") (pinfunction "1_P$1") (pintype "passive"))
      (node (ref "R21") (pin "P$1") (pinfunction "1_P$1") (pintype "passive"))
      (node (ref "R22") (pin "P$1") (pinfunction "1_P$1") (pintype "passive"))
      (node (ref "R23") (pin "P$1") (pinfunction "1_P$1") (pintype "passive"))
      (node (ref "R24") (pin "P$1") (pinfunction "1_P$1") (pintype "passive"))
      (node (ref "RJ1") (pin "10") (pinfunction "GLO_10") (pintype "bidirectional"))
      (node (ref "RJ1") (pin "8") (pinfunction "P8_8") (pintype "bidirectional"))
      (node (ref "U1") (pin "22") (pinfunction "GND_22") (pintype "power_in"))
      (node (ref "U1") (pin "25") (pinfunction "25_25") (pintype "passive"))
      (node (ref "U2") (pin "2") (pinfunction "GND_2") (pintype "input"))
      (node (ref "U3") (pin "111") (pinfunction "VSS(IO)5_111") (pintype "bidirectional"))
      (node (ref "U3") (pin "124") (pinfunction "VSS(IO)6_124") (pintype "bidirectional"))
      (node (ref "U3") (pin "139") (pinfunction "VSS(IO)7_139") (pintype "bidirectional"))
      (node (ref "U3") (pin "150") (pinfunction "VSS(IO)8_150") (pintype "bidirectional"))
      (node (ref "U3") (pin "153") (pinfunction "VREFL_153") (pintype "bidirectional"))
      (node (ref "U3") (pin "156") (pinfunction "AVSS0_156") (pintype "bidirectional"))
      (node (ref "U3") (pin "157") (pinfunction "VREFL0_157") (pintype "bidirectional"))
      (node (ref "U3") (pin "170") (pinfunction "VSS(IO)9_170") (pintype "bidirectional"))
      (node (ref "U3") (pin "22") (pinfunction "VSS1_22") (pintype "bidirectional"))
      (node (ref "U3") (pin "28") (pinfunction "AVSS_USBHS_28") (pintype "bidirectional"))
      (node (ref "U3") (pin "29") (pinfunction "PVSS_USBHS_29") (pintype "bidirectional"))
      (node (ref "U3") (pin "30") (pinfunction "VSS2_USBHS_30") (pintype "bidirectional"))
      (node (ref "U3") (pin "33") (pinfunction "VSS1_USBHS_33") (pintype "bidirectional"))
      (node (ref "U3") (pin "35") (pinfunction "VSSIO_35") (pintype "bidirectional"))
      (node (ref "U3") (pin "45") (pinfunction "VSS_USB_45") (pintype "bidirectional"))
      (node (ref "U3") (pin "60") (pinfunction "VSS(IO)2_60") (pintype "bidirectional"))
      (node (ref "U3") (pin "63") (pinfunction "VSS(IO/DCDC)_63") (pintype "bidirectional"))
      (node (ref "U3") (pin "66") (pinfunction "VCC_DCDC(IO/DCDC)_66") (pintype "bidirectional"))
      (node (ref "U3") (pin "83") (pinfunction "VSS(IO)3_83") (pintype "bidirectional"))
      (node (ref "U3") (pin "98") (pinfunction "VSS(IO)4_98") (pintype "bidirectional"))
      (node (ref "X1") (pin "2") (pinfunction "2_2") (pintype "bidirectional"))
      (node (ref "X1") (pin "4") (pinfunction "4_4") (pintype "bidirectional"))
      (node (ref "X2") (pin "2") (pinfunction "2_2") (pintype "bidirectional"))
      (node (ref "X2") (pin "4") (pinfunction "4_4") (pintype "bidirectional"))
    )
    (net (code "17") (name "GNDE") (class "Default")
      (node (ref "J1") (pin "S1") (pinfunction "SHIELD_S1") (pintype "passive"))
      (node (ref "J1") (pin "S2") (pinfunction "SHIELD_S2") (pintype "passive"))
      (node (ref "J1") (pin "S3") (pinfunction "SHIELD_S3") (pintype "passive"))
      (node (ref "J1") (pin "S4") (pinfunction "SHIELD_S4") (pintype "passive"))
      (node (ref "J2") (pin "P$4") (pinfunction "P$4_P$4") (pintype "bidirectional"))
      (node (ref "J6") (pin "SHLD1") (pinfunction "SHIELD_1_SHLD1") (pintype "bidirectional"))
      (node (ref "J6") (pin "SHLD2") (pinfunction "SHIELD_2_SHLD2") (pintype "bidirectional"))
      (node (ref "J7") (pin "P$6") (pinfunction "SHIELD1_P$6") (pintype "bidirectional"))
      (node (ref "J7") (pin "P$7") (pinfunction "SHIELD2_P$7") (pintype "bidirectional"))
      (node (ref "J7") (pin "P$8") (pinfunction "SHIELD3_P$8") (pintype "bidirectional"))
      (node (ref "J7") (pin "P$9") (pinfunction "SHIELD4_P$9") (pintype "bidirectional"))
      (node (ref "RJ1") (pin "13") (pinfunction "GNDE0_13") (pintype "bidirectional"))
      (node (ref "RJ1") (pin "14") (pinfunction "GNDE1_14") (pintype "bidirectional"))
    )
    (net (code "18") (name "ID") (class "Default")
      (node (ref "J7") (pin "P$4") (pinfunction "ID_P$4") (pintype "bidirectional"))
    )
    (net (code "19") (name "IIC_1_SCL") (class "Default")
      (node (ref "J8") (pin "P$5") (pinfunction "P$5_P$5") (pintype "bidirectional"))
      (node (ref "R14") (pin "P$2") (pinfunction "2_P$2") (pintype "passive"))
      (node (ref "U3") (pin "132") (pinfunction "P1_0_132") (pintype "bidirectional"))
    )
    (net (code "20") (name "IIC_1_SDA") (class "Default")
      (node (ref "J8") (pin "P$6") (pinfunction "P$6_P$6") (pintype "bidirectional"))
      (node (ref "R15") (pin "P$2") (pinfunction "2_P$2") (pintype "passive"))
      (node (ref "U3") (pin "131") (pinfunction "P1_1_131") (pintype "bidirectional"))
    )
    (net (code "21") (name "INT_MI_01") (class "Default")
      (node (ref "J8") (pin "P$39") (pinfunction "P$39_P$39") (pintype "bidirectional"))
      (node (ref "U3") (pin "87") (pinfunction "P3_1_87") (pintype "bidirectional"))
    )
    (net (code "22") (name "INT_MI_02") (class "Default")
      (node (ref "J8") (pin "P$40") (pinfunction "P$40_P$40") (pintype "bidirectional"))
      (node (ref "U3") (pin "86") (pinfunction "P3_2_86") (pintype "bidirectional"))
    )
    (net (code "23") (name "INT_MI_03") (class "Default")
      (node (ref "J8") (pin "P$9") (pinfunction "P$9_P$9") (pintype "bidirectional"))
      (node (ref "U3") (pin "128") (pinfunction "P1_4_128") (pintype "bidirectional"))
    )
    (net (code "24") (name "INT_MI_04") (class "Default")
      (node (ref "J8") (pin "P$10") (pinfunction "P$10_P$10") (pintype "bidirectional"))
      (node (ref "U3") (pin "127") (pinfunction "P1_5_127") (pintype "bidirectional"))
    )
    (net (code "25") (name "LED1{slash}SPEED") (class "Default")
      (node (ref "RJ1") (pin "11") (pinfunction "YLO_11") (pintype "bidirectional"))
      (node (ref "U1") (pin "23") (pinfunction "LED0/ANEN_SPEED_23") (pintype "bidirectional"))
    )
    (net (code "26") (name "NC") (class "Default")
      (node (ref "RJ1") (pin "7") (pinfunction "P7_7") (pintype "bidirectional"))
    )
    (net (code "27") (name "Net-(C8-1)") (class "Default")
      (node (ref "C8") (pin "P$1") (pinfunction "1_P$1") (pintype "passive"))
      (node (ref "C9") (pin "P$1") (pinfunction "1_P$1") (pintype "passive"))
      (node (ref "FB1") (pin "2") (pinfunction "P$2_2") (pintype "bidirectional"))
      (node (ref "U1") (pin "2") (pinfunction "VDDA_3.3_2") (pintype "power_in"))
    )
    (net (code "28") (name "Net-(C24-2)") (class "Default")
      (node (ref "C24") (pin "P$2") (pinfunction "2_P$2") (pintype "passive"))
      (node (ref "U3") (pin "148") (pinfunction "VCL2_148") (pintype "bidirectional"))
    )
    (net (code "29") (name "Net-(C28-1)") (class "Default")
      (node (ref "C28") (pin "P$1") (pinfunction "1_P$1") (pintype "passive"))
      (node (ref "J7") (pin "P$1") (pinfunction "VBUS_P$1") (pintype "bidirectional"))
      (node (ref "R16") (pin "P$2") (pinfunction "2_P$2") (pintype "passive"))
      (node (ref "R21") (pin "P$2") (pinfunction "2_P$2") (pintype "passive"))
    )
    (net (code "30") (name "Net-(C33-1)") (class "Default")
      (node (ref "C33") (pin "P$1") (pinfunction "1_P$1") (pintype "passive"))
      (node (ref "U3") (pin "19") (pinfunction "VCLO_19") (pintype "bidirectional"))
    )
    (net (code "31") (name "Net-(C42-1)") (class "Default")
      (node (ref "C42") (pin "P$1") (pinfunction "1_P$1") (pintype "passive"))
      (node (ref "U3") (pin "62") (pinfunction "VCL1_62") (pintype "bidirectional"))
    )
    (net (code "32") (name "Net-(J7-D+)") (class "Default")
      (node (ref "J7") (pin "P$3") (pinfunction "D+_P$3") (pintype "bidirectional"))
      (node (ref "R18") (pin "P$2") (pinfunction "2_P$2") (pintype "passive"))
    )
    (net (code "33") (name "Net-(J7-D-)") (class "Default")
      (node (ref "J7") (pin "P$2") (pinfunction "D-_P$2") (pintype "bidirectional"))
      (node (ref "R17") (pin "P$2") (pinfunction "2_P$2") (pintype "passive"))
    )
    (net (code "34") (name "Net-(LED1-A)") (class "Default")
      (node (ref "LED1") (pin "1") (pinfunction "A_1") (pintype "passive"))
      (node (ref "R5") (pin "P$1") (pinfunction "1_P$1") (pintype "passive"))
    )
    (net (code "35") (name "Net-(R22-2)") (class "Default")
      (node (ref "R22") (pin "P$2") (pinfunction "2_P$2") (pintype "passive"))
      (node (ref "U3") (pin "27") (pinfunction "USBHS_RREF_27") (pintype "bidirectional"))
    )
    (net (code "36") (name "Net-(R23-2)") (class "Default")
      (node (ref "R23") (pin "P$2") (pinfunction "2_P$2") (pintype "passive"))
      (node (ref "U3") (pin "64") (pinfunction "VLO1(DCDC)_64") (pintype "bidirectional"))
    )
    (net (code "37") (name "Net-(R24-2)") (class "Default")
      (node (ref "R24") (pin "P$2") (pinfunction "2_P$2") (pintype "passive"))
      (node (ref "U3") (pin "65") (pinfunction "VLO2(DCDC)_65") (pintype "bidirectional"))
    )
    (net (code "38") (name "P0_00") (class "Default")
      (node (ref "J4") (pin "P$2") (pinfunction "P$2_P$2") (pintype "bidirectional"))
      (node (ref "U3") (pin "169") (pinfunction "P0_0/AN0\\00_169") (pintype "bidirectional"))
    )
    (net (code "39") (name "P0_01") (class "Default")
      (node (ref "J4") (pin "P$1") (pinfunction "P$1_P$1") (pintype "bidirectional"))
      (node (ref "U3") (pin "168") (pinfunction "P0_1/AN001_168") (pintype "bidirectional"))
    )
    (net (code "40") (name "P0_02") (class "Default")
      (node (ref "J5") (pin "1") (pinfunction "1_1") (pintype "passive"))
      (node (ref "U3") (pin "167") (pinfunction "P0_2/AN002_167") (pintype "bidirectional"))
    )
    (net (code "41") (name "P0_03") (class "Default")
      (node (ref "J5") (pin "3") (pinfunction "3_3") (pintype "passive"))
      (node (ref "U3") (pin "166") (pinfunction "P0_3/PGAVSS000_166") (pintype "bidirectional"))
    )
    (net (code "42") (name "P0_04") (class "Default")
      (node (ref "J5") (pin "5") (pinfunction "5_5") (pintype "passive"))
      (node (ref "U3") (pin "165") (pinfunction "P0_4/AN100_165") (pintype "bidirectional"))
    )
    (net (code "43") (name "P0_05") (class "Default")
      (node (ref "J5") (pin "7") (pinfunction "7_7") (pintype "passive"))
      (node (ref "U3") (pin "164") (pinfunction "P0_5/AN101_164") (pintype "bidirectional"))
    )
    (net (code "44") (name "P0_06") (class "Default")
      (node (ref "J5") (pin "9") (pinfunction "9_9") (pintype "passive"))
      (node (ref "U3") (pin "163") (pinfunction "P0_6/AN102_163") (pintype "bidirectional"))
    )
    (net (code "45") (name "P0_07") (class "Default")
      (node (ref "J5") (pin "10") (pinfunction "10_10") (pintype "passive"))
      (node (ref "U3") (pin "162") (pinfunction "P0_7/PGVSS100_162") (pintype "bidirectional"))
    )
    (net (code "46") (name "P0_08") (class "Default")
      (node (ref "J5") (pin "8") (pinfunction "8_8") (pintype "passive"))
      (node (ref "U3") (pin "161") (pinfunction "P0_8/AN003_161") (pintype "bidirectional"))
    )
    (net (code "47") (name "P0_09") (class "Default")
      (node (ref "J5") (pin "6") (pinfunction "6_6") (pintype "passive"))
      (node (ref "U3") (pin "160") (pinfunction "P0_9/AN004_160") (pintype "bidirectional"))
    )
    (net (code "48") (name "P0_14") (class "Default")
      (node (ref "J5") (pin "4") (pinfunction "4_4") (pintype "passive"))
      (node (ref "U3") (pin "152") (pinfunction "P0_14/DA0/AN005/AN105_152") (pintype "bidirectional"))
    )
    (net (code "49") (name "P0_15") (class "Default")
      (node (ref "J5") (pin "2") (pinfunction "2_2") (pintype "passive"))
      (node (ref "U3") (pin "151") (pinfunction "P0_15/DA1/AN006/AN106_151") (pintype "bidirectional"))
    )
    (net (code "50") (name "P1_02") (class "Default")
      (node (ref "J8") (pin "P$7") (pinfunction "P$7_P$7") (pintype "bidirectional"))
      (node (ref "U3") (pin "130") (pinfunction "P1_2_130") (pintype "bidirectional"))
    )
    (net (code "51") (name "P1_03") (class "Default")
      (node (ref "J8") (pin "P$8") (pinfunction "P$8_P$8") (pintype "bidirectional"))
      (node (ref "U3") (pin "129") (pinfunction "P1_3_129") (pintype "bidirectional"))
    )
    (net (code "52") (name "P1_06") (class "Default")
      (node (ref "J8") (pin "P$11") (pinfunction "P$11_P$11") (pintype "bidirectional"))
      (node (ref "U3") (pin "126") (pinfunction "P1_6_126") (pintype "bidirectional"))
    )
    (net (code "53") (name "P1_07") (class "Default")
      (node (ref "J8") (pin "P$12") (pinfunction "P$12_P$12") (pintype "bidirectional"))
      (node (ref "U3") (pin "125") (pinfunction "P1_7_125") (pintype "bidirectional"))
    )
    (net (code "54") (name "P1_11") (class "Default")
      (node (ref "J8") (pin "P$38") (pinfunction "P$38_P$38") (pintype "bidirectional"))
      (node (ref "U3") (pin "92") (pinfunction "P1_11_92") (pintype "bidirectional"))
    )
    (net (code "55") (name "P1_12") (class "Default")
      (node (ref "J8") (pin "P$37") (pinfunction "P$37_P$37") (pintype "bidirectional"))
      (node (ref "U3") (pin "93") (pinfunction "P1_12_93") (pintype "bidirectional"))
    )
    (net (code "56") (name "P1_13") (class "Default")
      (node (ref "J8") (pin "P$36") (pinfunction "P$36_P$36") (pintype "bidirectional"))
      (node (ref "U3") (pin "94") (pinfunction "P1_13_94") (pintype "bidirectional"))
    )
    (net (code "57") (name "P1_14") (class "Default")
      (node (ref "J8") (pin "P$35") (pinfunction "P$35_P$35") (pintype "bidirectional"))
      (node (ref "U3") (pin "95") (pinfunction "P1_14_95") (pintype "bidirectional"))
    )
    (net (code "58") (name "P1_15") (class "Default")
      (node (ref "J8") (pin "P$34") (pinfunction "P$34_P$34") (pintype "bidirectional"))
      (node (ref "U3") (pin "96") (pinfunction "P1_15_96") (pintype "bidirectional"))
    )
    (net (code "59") (name "P2_00") (class "Default")
      (node (ref "J10") (pin "P$13") (pinfunction "P$13_P$13") (pintype "bidirectional"))
      (node (ref "U3") (pin "69") (pinfunction "P2_0(INPUT_ONLY)_69") (pintype "bidirectional"))
    )
    (net (code "60") (name "P2_01") (class "Default")
      (node (ref "J10") (pin "P$14") (pinfunction "P$14_P$14") (pintype "bidirectional"))
      (node (ref "U3") (pin "68") (pinfunction "P2_1/MD_68") (pintype "bidirectional"))
    )
    (net (code "61") (name "P2_02") (class "Default")
      (node (ref "J10") (pin "P$19") (pinfunction "P$19_P$19") (pintype "bidirectional"))
      (node (ref "U3") (pin "54") (pinfunction "P2_2_54") (pintype "bidirectional"))
    )
    (net (code "62") (name "P2_03") (class "Default")
      (node (ref "J9") (pin "1") (pinfunction "1_1") (pintype "passive"))
      (node (ref "U3") (pin "53") (pinfunction "P2_3_53") (pintype "bidirectional"))
    )
    (net (code "63") (name "P2_04") (class "Default")
      (node (ref "J9") (pin "3") (pinfunction "3_3") (pintype "passive"))
      (node (ref "U3") (pin "52") (pinfunction "P2_4_52") (pintype "bidirectional"))
    )
    (net (code "64") (name "P2_05") (class "Default")
      (node (ref "J9") (pin "5") (pinfunction "5_5") (pintype "passive"))
      (node (ref "U3") (pin "51") (pinfunction "P2_5_51") (pintype "bidirectional"))
    )
    (net (code "65") (name "P2_06") (class "Default")
      (node (ref "J9") (pin "7") (pinfunction "7_7") (pintype "passive"))
      (node (ref "U3") (pin "50") (pinfunction "P2_6_50") (pintype "bidirectional"))
    )
    (net (code "66") (name "P2_07") (class "Default")
      (node (ref "J9") (pin "9") (pinfunction "9_9") (pintype "passive"))
      (node (ref "U3") (pin "49") (pinfunction "P2_7_49") (pintype "bidirectional"))
    )
    (net (code "67") (name "P3_03") (class "Default")
      (node (ref "J10") (pin "P$2") (pinfunction "P$2_P$2") (pintype "bidirectional"))
      (node (ref "U3") (pin "85") (pinfunction "P3_3_85") (pintype "bidirectional"))
    )
    (net (code "68") (name "P3_04") (class "Default")
      (node (ref "J10") (pin "P$4") (pinfunction "P$4_P$4") (pintype "bidirectional"))
      (node (ref "U3") (pin "82") (pinfunction "P3_4_82") (pintype "bidirectional"))
    )
    (net (code "69") (name "P3_05") (class "Default")
      (node (ref "J10") (pin "P$6") (pinfunction "P$6_P$6") (pintype "bidirectional"))
      (node (ref "U3") (pin "81") (pinfunction "P3_5_81") (pintype "bidirectional"))
    )
    (net (code "70") (name "P3_06") (class "Default")
      (node (ref "J10") (pin "P$1") (pinfunction "P$1_P$1") (pintype "bidirectional"))
      (node (ref "U3") (pin "80") (pinfunction "P3_6_80") (pintype "bidirectional"))
    )
    (net (code "71") (name "P3_07") (class "Default")
      (node (ref "J10") (pin "P$3") (pinfunction "P$3_P$3") (pintype "bidirectional"))
      (node (ref "U3") (pin "79") (pinfunction "P3_7_79") (pintype "bidirectional"))
    )
    (net (code "72") (name "P3_09") (class "Default")
      (node (ref "J10") (pin "P$5") (pinfunction "P$5_P$5") (pintype "bidirectional"))
      (node (ref "U3") (pin "77") (pinfunction "P3_9_77") (pintype "bidirectional"))
    )
    (net (code "73") (name "P3_10") (class "Default")
      (node (ref "J10") (pin "P$7") (pinfunction "P$7_P$7") (pintype "bidirectional"))
      (node (ref "U3") (pin "76") (pinfunction "P3_10_76") (pintype "bidirectional"))
    )
    (net (code "74") (name "P3_11") (class "Default")
      (node (ref "J10") (pin "P$8") (pinfunction "P$8_P$8") (pintype "bidirectional"))
      (node (ref "U3") (pin "75") (pinfunction "P3_11_75") (pintype "bidirectional"))
    )
    (net (code "75") (name "P3_12") (class "Default")
      (node (ref "J10") (pin "P$9") (pinfunction "P$9_P$9") (pintype "bidirectional"))
      (node (ref "U3") (pin "74") (pinfunction "P3_12_74") (pintype "bidirectional"))
    )
    (net (code "76") (name "P3_13") (class "Default")
      (node (ref "J10") (pin "P$20") (pinfunction "P$20_P$20") (pintype "bidirectional"))
      (node (ref "U3") (pin "55") (pinfunction "P3_13_55") (pintype "bidirectional"))
    )
    (net (code "77") (name "P3_14") (class "Default")
      (node (ref "J10") (pin "P$17") (pinfunction "P$17_P$17") (pintype "bidirectional"))
      (node (ref "U3") (pin "56") (pinfunction "P3_14_56") (pintype "bidirectional"))
    )
    (net (code "78") (name "P3_15") (class "Default")
      (node (ref "J10") (pin "P$18") (pinfunction "P$18_P$18") (pintype "bidirectional"))
      (node (ref "U3") (pin "57") (pinfunction "P3_15_57") (pintype "bidirectional"))
    )
    (net (code "79") (name "P4_00") (class "Default")
      (node (ref "J4") (pin "P$7") (pinfunction "P$7_P$7") (pintype "bidirectional"))
      (node (ref "U3") (pin "1") (pinfunction "P4_0_1") (pintype "bidirectional"))
    )
    (net (code "80") (name "P4_01") (class "Default")
      (node (ref "J4") (pin "P$8") (pinfunction "P$8_P$8") (pintype "bidirectional"))
      (node (ref "U3") (pin "2") (pinfunction "P4_1_2") (pintype "bidirectional"))
    )
    (net (code "81") (name "P4_02") (class "Default")
      (node (ref "J4") (pin "P$9") (pinfunction "P$9_P$9") (pintype "bidirectional"))
      (node (ref "U3") (pin "3") (pinfunction "P4_2_3") (pintype "bidirectional"))
    )
    (net (code "82") (name "P4_08") (class "Default")
      (node (ref "J4") (pin "P$20") (pinfunction "P$20_P$20") (pintype "bidirectional"))
      (node (ref "U3") (pin "43") (pinfunction "P4_8_43") (pintype "bidirectional"))
    )
    (net (code "83") (name "P4_09") (class "Default")
      (node (ref "J4") (pin "P$19") (pinfunction "P$19_P$19") (pintype "bidirectional"))
      (node (ref "U3") (pin "42") (pinfunction "P4_9_42") (pintype "bidirectional"))
    )
    (net (code "84") (name "P4_10") (class "Default")
      (node (ref "J4") (pin "P$18") (pinfunction "P$18_P$18") (pintype "bidirectional"))
      (node (ref "U3") (pin "41") (pinfunction "P4_10_41") (pintype "bidirectional"))
    )
    (net (code "85") (name "P4_11") (class "Default")
      (node (ref "J4") (pin "P$17") (pinfunction "P$17_P$17") (pintype "bidirectional"))
      (node (ref "U3") (pin "40") (pinfunction "P4_11_40") (pintype "bidirectional"))
    )
    (net (code "86") (name "P4_12") (class "Default")
      (node (ref "J4") (pin "P$16") (pinfunction "P$16_P$16") (pintype "bidirectional"))
      (node (ref "U3") (pin "39") (pinfunction "P4_12_39") (pintype "bidirectional"))
    )
    (net (code "87") (name "P4_13") (class "Default")
      (node (ref "J4") (pin "P$15") (pinfunction "P$15_P$15") (pintype "bidirectional"))
      (node (ref "U3") (pin "38") (pinfunction "P4_13_38") (pintype "bidirectional"))
    )
    (net (code "88") (name "P4_14") (class "Default")
      (node (ref "J4") (pin "P$14") (pinfunction "P$14_P$14") (pintype "bidirectional"))
      (node (ref "U3") (pin "37") (pinfunction "P4_14_37") (pintype "bidirectional"))
    )
    (net (code "89") (name "P4_15") (class "Default")
      (node (ref "J4") (pin "P$13") (pinfunction "P$13_P$13") (pintype "bidirectional"))
      (node (ref "U3") (pin "36") (pinfunction "P4_15_36") (pintype "bidirectional"))
    )
    (net (code "90") (name "P5_11") (class "Default")
      (node (ref "J4") (pin "P$6") (pinfunction "P$6_P$6") (pintype "bidirectional"))
      (node (ref "U3") (pin "176") (pinfunction "P5_11_176") (pintype "bidirectional"))
    )
    (net (code "91") (name "P5_12") (class "Default")
      (node (ref "J4") (pin "P$5") (pinfunction "P$5_P$5") (pintype "bidirectional"))
      (node (ref "U3") (pin "175") (pinfunction "P5_12_175") (pintype "bidirectional"))
    )
    (net (code "92") (name "P5_13") (class "Default")
      (node (ref "J4") (pin "P$4") (pinfunction "P$4_P$4") (pintype "bidirectional"))
      (node (ref "U3") (pin "174") (pinfunction "P5_13_174") (pintype "bidirectional"))
    )
    (net (code "93") (name "P6_00") (class "Default")
      (node (ref "J8") (pin "P$13") (pinfunction "P$13_P$13") (pintype "bidirectional"))
      (node (ref "U3") (pin "122") (pinfunction "P6_0_122") (pintype "bidirectional"))
    )
    (net (code "94") (name "P6_01") (class "Default")
      (node (ref "J8") (pin "P$14") (pinfunction "P$14_P$14") (pintype "bidirectional"))
      (node (ref "U3") (pin "121") (pinfunction "P6_1_121") (pintype "bidirectional"))
    )
    (net (code "95") (name "P6_02") (class "Default")
      (node (ref "J8") (pin "P$15") (pinfunction "P$15_P$15") (pintype "bidirectional"))
      (node (ref "U3") (pin "120") (pinfunction "P6_2_120") (pintype "bidirectional"))
    )
    (net (code "96") (name "P6_03") (class "Default")
      (node (ref "J8") (pin "P$16") (pinfunction "P$16_P$16") (pintype "bidirectional"))
      (node (ref "U3") (pin "119") (pinfunction "P6_3_119") (pintype "bidirectional"))
    )
    (net (code "97") (name "P6_04") (class "Default")
      (node (ref "J8") (pin "P$17") (pinfunction "P$17_P$17") (pintype "bidirectional"))
      (node (ref "U3") (pin "118") (pinfunction "P6_4_118") (pintype "bidirectional"))
    )
    (net (code "98") (name "P6_05") (class "Default")
      (node (ref "J8") (pin "P$18") (pinfunction "P$18_P$18") (pintype "bidirectional"))
      (node (ref "U3") (pin "117") (pinfunction "P6_5_117") (pintype "bidirectional"))
    )
    (net (code "99") (name "P6_06") (class "Default")
      (node (ref "J8") (pin "P$19") (pinfunction "P$19_P$19") (pintype "bidirectional"))
      (node (ref "U3") (pin "116") (pinfunction "P6_6_116") (pintype "bidirectional"))
    )
    (net (code "100") (name "P6_07") (class "Default")
      (node (ref "J8") (pin "P$20") (pinfunction "P$20_P$20") (pintype "bidirectional"))
      (node (ref "U3") (pin "115") (pinfunction "P6_7_115") (pintype "bidirectional"))
    )
    (net (code "101") (name "P6_08") (class "Default")
      (node (ref "J8") (pin "P$33") (pinfunction "P$33_P$33") (pintype "bidirectional"))
      (node (ref "U3") (pin "99") (pinfunction "P6_8_99") (pintype "bidirectional"))
    )
    (net (code "102") (name "P6_09") (class "Default")
      (node (ref "J8") (pin "P$32") (pinfunction "P$32_P$32") (pintype "bidirectional"))
      (node (ref "U3") (pin "100") (pinfunction "P6_9_100") (pintype "bidirectional"))
    )
    (net (code "103") (name "P6_10") (class "Default")
      (node (ref "J8") (pin "P$31") (pinfunction "P$31_P$31") (pintype "bidirectional"))
      (node (ref "U3") (pin "101") (pinfunction "P6_10_101") (pintype "bidirectional"))
    )
    (net (code "104") (name "P6_11") (class "Default")
      (node (ref "J8") (pin "P$30") (pinfunction "P$30_P$30") (pintype "bidirectional"))
      (node (ref "U3") (pin "102") (pinfunction "P6_11_102") (pintype "bidirectional"))
    )
    (net (code "105") (name "P6_12") (class "Default")
      (node (ref "J8") (pin "P$29") (pinfunction "P$29_P$29") (pintype "bidirectional"))
      (node (ref "U3") (pin "103") (pinfunction "P6_12_103") (pintype "bidirectional"))
    )
    (net (code "106") (name "P6_13") (class "Default")
      (node (ref "J8") (pin "P$28") (pinfunction "P$28_P$28") (pintype "bidirectional"))
      (node (ref "U3") (pin "104") (pinfunction "P6_13_104") (pintype "bidirectional"))
    )
    (net (code "107") (name "P6_14") (class "Default")
      (node (ref "J8") (pin "P$27") (pinfunction "P$27_P$27") (pintype "bidirectional"))
      (node (ref "U3") (pin "105") (pinfunction "P6_14_105") (pintype "bidirectional"))
    )
    (net (code "108") (name "P6_15") (class "Default")
      (node (ref "J8") (pin "P$26") (pinfunction "P$26_P$26") (pintype "bidirectional"))
      (node (ref "U3") (pin "106") (pinfunction "P6_15_106") (pintype "bidirectional"))
    )
    (net (code "109") (name "P7_06") (class "Default")
      (node (ref "J4") (pin "P$10") (pinfunction "P$10_P$10") (pintype "bidirectional"))
      (node (ref "U3") (pin "14") (pinfunction "P7_6_14") (pintype "bidirectional"))
    )
    (net (code "110") (name "P7_07") (class "Default")
      (node (ref "J4") (pin "P$11") (pinfunction "P$11_P$11") (pintype "bidirectional"))
      (node (ref "U3") (pin "15") (pinfunction "P7_7_15") (pintype "bidirectional"))
    )
    (net (code "111") (name "P8_00") (class "Default")
      (node (ref "J8") (pin "P$4") (pinfunction "P$4_P$4") (pintype "bidirectional"))
      (node (ref "U3") (pin "133") (pinfunction "P8_0_133") (pintype "bidirectional"))
    )
    (net (code "112") (name "P8_01") (class "Default")
      (node (ref "J8") (pin "P$3") (pinfunction "P$3_P$3") (pintype "bidirectional"))
      (node (ref "U3") (pin "134") (pinfunction "P8_1_134") (pintype "bidirectional"))
    )
    (net (code "113") (name "P8_02") (class "Default")
      (node (ref "J8") (pin "P$2") (pinfunction "P$2_P$2") (pintype "bidirectional"))
      (node (ref "U3") (pin "135") (pinfunction "P8_2_135") (pintype "bidirectional"))
    )
    (net (code "114") (name "P8_03") (class "Default")
      (node (ref "U3") (pin "136") (pinfunction "P8_3_136") (pintype "bidirectional"))
    )
    (net (code "115") (name "P8_04") (class "Default")
      (node (ref "U3") (pin "137") (pinfunction "P8_4_137") (pintype "bidirectional"))
    )
    (net (code "116") (name "P8_05") (class "Default")
      (node (ref "J4") (pin "P$3") (pinfunction "P$3_P$3") (pintype "bidirectional"))
      (node (ref "U3") (pin "173") (pinfunction "P8_5_173") (pintype "bidirectional"))
    )
    (net (code "117") (name "P9_00") (class "Default")
      (node (ref "J10") (pin "P$16") (pinfunction "P$16_P$16") (pintype "bidirectional"))
      (node (ref "U3") (pin "58") (pinfunction "P9_0_58") (pintype "bidirectional"))
    )
    (net (code "118") (name "P9_01") (class "Default")
      (node (ref "J10") (pin "P$15") (pinfunction "P$15_P$15") (pintype "bidirectional"))
      (node (ref "U3") (pin "59") (pinfunction "P9_1_59") (pintype "bidirectional"))
    )
    (net (code "119") (name "P9_05") (class "Default")
      (node (ref "J10") (pin "P$10") (pinfunction "P$10_P$10") (pintype "bidirectional"))
      (node (ref "U3") (pin "73") (pinfunction "P9_5_73") (pintype "bidirectional"))
    )
    (net (code "120") (name "P9_06") (class "Default")
      (node (ref "J10") (pin "P$11") (pinfunction "P$11_P$11") (pintype "bidirectional"))
      (node (ref "U3") (pin "72") (pinfunction "P9_6_72") (pintype "bidirectional"))
    )
    (net (code "121") (name "P9_07") (class "Default")
      (node (ref "J10") (pin "P$12") (pinfunction "P$12_P$12") (pintype "bidirectional"))
      (node (ref "U3") (pin "71") (pinfunction "P9_7_71") (pintype "bidirectional"))
    )
    (net (code "122") (name "P9_08") (class "Default")
      (node (ref "U3") (pin "70") (pinfunction "P9_8_70") (pintype "bidirectional"))
    )
    (net (code "123") (name "PA_00") (class "Default")
      (node (ref "J8") (pin "P$21") (pinfunction "P$21_P$21") (pintype "bidirectional"))
      (node (ref "U3") (pin "114") (pinfunction "PA_0_114") (pintype "bidirectional"))
    )
    (net (code "124") (name "PA_01") (class "Default")
      (node (ref "J8") (pin "P$22") (pinfunction "P$22_P$22") (pintype "bidirectional"))
      (node (ref "U3") (pin "113") (pinfunction "PA_1_113") (pintype "bidirectional"))
    )
    (net (code "125") (name "PA_08") (class "Default")
      (node (ref "J8") (pin "P$25") (pinfunction "P$25_P$25") (pintype "bidirectional"))
      (node (ref "U3") (pin "107") (pinfunction "PA_8_107") (pintype "bidirectional"))
    )
    (net (code "126") (name "PA_09") (class "Default")
      (node (ref "J8") (pin "P$24") (pinfunction "P$24_P$24") (pintype "bidirectional"))
      (node (ref "U3") (pin "108") (pinfunction "PA_9_108") (pintype "bidirectional"))
    )
    (net (code "127") (name "PA_10") (class "Default")
      (node (ref "J8") (pin "P$23") (pinfunction "P$23_P$23") (pintype "bidirectional"))
      (node (ref "U3") (pin "109") (pinfunction "PA_10_109") (pintype "bidirectional"))
    )
    (net (code "128") (name "PB_00") (class "Default")
      (node (ref "J4") (pin "P$12") (pinfunction "P$12_P$12") (pintype "bidirectional"))
      (node (ref "U3") (pin "16") (pinfunction "PB_0_16") (pintype "bidirectional"))
    )
    (net (code "129") (name "R51") (class "Default")
      (node (ref "R7") (pin "P$1") (pinfunction "1_P$1") (pintype "passive"))
      (node (ref "RJ1") (pin "12") (pinfunction "YHI_12") (pintype "bidirectional"))
    )
    (net (code "130") (name "R52") (class "Default")
      (node (ref "R8") (pin "P$1") (pinfunction "1_P$1") (pintype "passive"))
      (node (ref "RJ1") (pin "9") (pinfunction "GHI_9") (pintype "bidirectional"))
    )
    (net (code "131") (name "RESET") (class "Default")
      (node (ref "C16") (pin "P$1") (pinfunction "1_P$1") (pintype "passive"))
      (node (ref "J3") (pin "9") (pinfunction "9_9") (pintype "passive"))
      (node (ref "R13") (pin "P$1") (pinfunction "1_P$1") (pintype "passive"))
      (node (ref "U3") (pin "67") (pinfunction "RES#_67") (pintype "bidirectional"))
    )
    (net (code "132") (name "REXT") (class "Default")
      (node (ref "C3") (pin "P$1") (pinfunction "1_P$1") (pintype "passive"))
      (node (ref "R1") (pin "P$2") (pinfunction "2_P$2") (pintype "passive"))
      (node (ref "U1") (pin "9") (pinfunction "REXT_9") (pintype "input"))
    )
    (net (code "133") (name "RXD0") (class "Default")
      (node (ref "R10") (pin "P$2") (pinfunction "2_P$2") (pintype "passive"))
      (node (ref "U1") (pin "13") (pinfunction "RXD0_13") (pintype "bidirectional"))
    )
    (net (code "134") (name "RXD1") (class "Default")
      (node (ref "R9") (pin "P$2") (pinfunction "2_P$2") (pintype "passive"))
      (node (ref "U1") (pin "12") (pinfunction "RXD1_12") (pintype "bidirectional"))
    )
    (net (code "135") (name "RXER") (class "Default")
      (node (ref "R11") (pin "P$2") (pinfunction "2_P$2") (pintype "passive"))
      (node (ref "U1") (pin "17") (pinfunction "RXER_17") (pintype "bidirectional"))
    )
    (net (code "136") (name "RXM") (class "Default")
      (node (ref "RJ1") (pin "6") (pinfunction "RD-_6") (pintype "bidirectional"))
      (node (ref "U1") (pin "3") (pinfunction "RXM_3") (pintype "bidirectional"))
    )
    (net (code "137") (name "RXP") (class "Default")
      (node (ref "RJ1") (pin "3") (pinfunction "RD+_3") (pintype "bidirectional"))
      (node (ref "U1") (pin "4") (pinfunction "RXP_4") (pintype "bidirectional"))
    )
    (net (code "138") (name "SD1_CD") (class "Default")
      (node (ref "J1") (pin "10") (pinfunction "CD_SWITCH2_10") (pintype "bidirectional"))
      (node (ref "U3") (pin "146") (pinfunction "P5_6/AN019_146") (pintype "bidirectional"))
    )
    (net (code "139") (name "SD1_CLK") (class "Default")
      (node (ref "J1") (pin "5") (pinfunction "CLOCK_5") (pintype "bidirectional"))
      (node (ref "U3") (pin "140") (pinfunction "P5_0/AN016_140") (pintype "bidirectional"))
    )
    (net (code "140") (name "SD1_CMD") (class "Default")
      (node (ref "J1") (pin "3") (pinfunction "COMMAND/RESPONSE_3") (pintype "bidirectional"))
      (node (ref "U3") (pin "141") (pinfunction "P5_1/AN116_141") (pintype "bidirectional"))
    )
    (net (code "141") (name "SD1_DAT0") (class "Default")
      (node (ref "J1") (pin "7") (pinfunction "DATA_LINE[BIT_0]_7") (pintype "bidirectional"))
      (node (ref "U3") (pin "142") (pinfunction "P5_2/AN017_142") (pintype "bidirectional"))
    )
    (net (code "142") (name "SD1_DAT1") (class "Default")
      (node (ref "J1") (pin "8") (pinfunction "DATA_LINE[BIT_1]_8") (pintype "bidirectional"))
      (node (ref "U3") (pin "143") (pinfunction "P5_3/AN117_143") (pintype "bidirectional"))
    )
    (net (code "143") (name "SD1_DAT2") (class "Default")
      (node (ref "J1") (pin "1") (pinfunction "DATA_LINE[BIT_2]_1") (pintype "bidirectional"))
      (node (ref "U3") (pin "144") (pinfunction "P5_4/AN018_144") (pintype "bidirectional"))
    )
    (net (code "144") (name "SD1_DAT3") (class "Default")
      (node (ref "J1") (pin "2") (pinfunction "CARD_DETECT/DATA_LINE[BIT_3]_2") (pintype "bidirectional"))
      (node (ref "U3") (pin "145") (pinfunction "P5_5/AN118_145") (pintype "bidirectional"))
    )
    (net (code "145") (name "SD1_WP") (class "Default")
      (node (ref "J1") (pin "9") (pinfunction "CD_SWITCH1_9") (pintype "bidirectional"))
      (node (ref "U3") (pin "147") (pinfunction "P5_7/AN119_147") (pintype "bidirectional"))
    )
    (net (code "146") (name "TCK") (class "Default")
      (node (ref "J3") (pin "7") (pinfunction "7_7") (pintype "passive"))
      (node (ref "U3") (pin "88") (pinfunction "P3_0_88") (pintype "bidirectional"))
    )
    (net (code "147") (name "TDI") (class "Default")
      (node (ref "J3") (pin "1") (pinfunction "1_1") (pintype "passive"))
      (node (ref "U3") (pin "91") (pinfunction "P1_10_91") (pintype "bidirectional"))
    )
    (net (code "148") (name "TDO") (class "Default")
      (node (ref "J3") (pin "3") (pinfunction "3_3") (pintype "passive"))
      (node (ref "U3") (pin "90") (pinfunction "P1_9_90") (pintype "bidirectional"))
    )
    (net (code "149") (name "TMS") (class "Default")
      (node (ref "J3") (pin "5") (pinfunction "5_5") (pintype "passive"))
      (node (ref "U3") (pin "89") (pinfunction "P1_8_89") (pintype "bidirectional"))
    )
    (net (code "150") (name "TXM") (class "Default")
      (node (ref "RJ1") (pin "2") (pinfunction "TD-_2") (pintype "bidirectional"))
      (node (ref "U1") (pin "5") (pinfunction "TXM_5") (pintype "bidirectional"))
    )
    (net (code "151") (name "TXP") (class "Default")
      (node (ref "RJ1") (pin "1") (pinfunction "TD+_1") (pintype "bidirectional"))
      (node (ref "U1") (pin "6") (pinfunction "TXP_6") (pintype "bidirectional"))
    )
    (net (code "152") (name "USBHS_FAULT") (class "Default")
      (node (ref "R19") (pin "P$1") (pinfunction "1_P$1") (pintype "passive"))
      (node (ref "U2") (pin "3") (pinfunction "FLG_3") (pintype "input"))
      (node (ref "U3") (pin "78") (pinfunction "P3_8_78") (pintype "bidirectional"))
    )
    (net (code "153") (name "USBHS_N") (class "Default")
      (node (ref "J6") (pin "D-") (pinfunction "D-_D-") (pintype "bidirectional"))
      (node (ref "U3") (pin "31") (pinfunction "USBHS_DM_31") (pintype "bidirectional"))
    )
    (net (code "154") (name "USBHS_P") (class "Default")
      (node (ref "J6") (pin "D+") (pinfunction "D+_D+") (pintype "bidirectional"))
      (node (ref "U3") (pin "32") (pinfunction "USBHS_DP_32") (pintype "bidirectional"))
    )
    (net (code "155") (name "USBHS_VBUS") (class "Default")
      (node (ref "C29") (pin "P$1") (pinfunction "1_P$1") (pintype "passive"))
      (node (ref "C31") (pin "1") (pinfunction "1_1") (pintype "passive"))
      (node (ref "J6") (pin "VBUS") (pinfunction "VBUS_VBUS") (pintype "power_in"))
      (node (ref "U2") (pin "5") (pinfunction "OUT_5") (pintype "input"))
      (node (ref "U3") (pin "17") (pinfunction "PB_1_17") (pintype "bidirectional"))
    )
    (net (code "156") (name "USBHS_VBUSEN") (class "Default")
      (node (ref "R20") (pin "P$1") (pinfunction "1_P$1") (pintype "passive"))
      (node (ref "U2") (pin "1") (pinfunction "EN_1") (pintype "input"))
    )
    (net (code "157") (name "USB_N") (class "Default")
      (node (ref "R17") (pin "P$1") (pinfunction "1_P$1") (pintype "passive"))
      (node (ref "U3") (pin "46") (pinfunction "USB_DM_46") (pintype "bidirectional"))
    )
    (net (code "158") (name "USB_P") (class "Default")
      (node (ref "R18") (pin "P$1") (pinfunction "1_P$1") (pintype "passive"))
      (node (ref "U3") (pin "47") (pinfunction "USB_DP_47") (pintype "bidirectional"))
    )
    (net (code "159") (name "USB_VBUS_B") (class "Default")
      (node (ref "R16") (pin "P$1") (pinfunction "1_P$1") (pintype "passive"))
      (node (ref "U3") (pin "44") (pinfunction "P4_7_44") (pintype "bidirectional"))
    )
    (net (code "160") (name "VCL_F(FLASH)") (class "Default")
      (node (ref "C34") (pin "P$2") (pinfunction "2_P$2") (pintype "passive"))
      (node (ref "U3") (pin "112") (pinfunction "VCL_F(FLASH)_112") (pintype "bidirectional"))
    )
    (net (code "161") (name "VDD") (class "Default")
      (node (ref "C14") (pin "P$1") (pinfunction "1_P$1") (pintype "passive"))
      (node (ref "C15") (pin "P$1") (pinfunction "1_P$1") (pintype "passive"))
      (node (ref "C19") (pin "P$2") (pinfunction "2_P$2") (pintype "passive"))
      (node (ref "C20") (pin "P$2") (pinfunction "2_P$2") (pintype "passive"))
      (node (ref "C21") (pin "P$2") (pinfunction "2_P$2") (pintype "passive"))
      (node (ref "C22") (pin "P$2") (pinfunction "2_P$2") (pintype "passive"))
      (node (ref "C25") (pin "P$2") (pinfunction "2_P$2") (pintype "passive"))
      (node (ref "C27") (pin "P$2") (pinfunction "2_P$2") (pintype "passive"))
      (node (ref "C30") (pin "P$2") (pinfunction "2_P$2") (pintype "passive"))
      (node (ref "C35") (pin "P$2") (pinfunction "2_P$2") (pintype "passive"))
      (node (ref "C36") (pin "P$1") (pinfunction "1_P$1") (pintype "passive"))
      (node (ref "C38") (pin "P$2") (pinfunction "2_P$2") (pintype "passive"))
      (node (ref "C39") (pin "P$1") (pinfunction "1_P$1") (pintype "passive"))
      (node (ref "C4") (pin "P$1") (pinfunction "1_P$1") (pintype "passive"))
      (node (ref "C40") (pin "P$1") (pinfunction "1_P$1") (pintype "passive"))
      (node (ref "C41") (pin "P$1") (pinfunction "1_P$1") (pintype "passive"))
      (node (ref "C43") (pin "P$2") (pinfunction "2_P$2") (pintype "passive"))
      (node (ref "C5") (pin "P$1") (pinfunction "1_P$1") (pintype "passive"))
      (node (ref "C7") (pin "P$1") (pinfunction "1_P$1") (pintype "passive"))
      (node (ref "FB1") (pin "1") (pinfunction "P$1_1") (pintype "bidirectional"))
      (node (ref "J1") (pin "4") (pinfunction "SUPPLY_VOLTAGE_4") (pintype "power_in"))
      (node (ref "J3") (pin "2") (pinfunction "2_2") (pintype "passive"))
      (node (ref "J3") (pin "4") (pinfunction "4_4") (pintype "passive"))
      (node (ref "L1") (pin "2") (pinfunction "P$2_2") (pintype "bidirectional"))
      (node (ref "R13") (pin "P$2") (pinfunction "2_P$2") (pintype "passive"))
      (node (ref "R14") (pin "P$1") (pinfunction "1_P$1") (pintype "passive"))
      (node (ref "R15") (pin "P$1") (pinfunction "1_P$1") (pintype "passive"))
      (node (ref "R2") (pin "P$2") (pinfunction "2_P$2") (pintype "passive"))
      (node (ref "R3") (pin "P$2") (pinfunction "2_P$2") (pintype "passive"))
      (node (ref "R4") (pin "P$2") (pinfunction "2_P$2") (pintype "passive"))
      (node (ref "R5") (pin "P$2") (pinfunction "2_P$2") (pintype "passive"))
      (node (ref "R6") (pin "P$2") (pinfunction "2_P$2") (pintype "passive"))
      (node (ref "R7") (pin "P$2") (pinfunction "2_P$2") (pintype "passive"))
      (node (ref "R8") (pin "P$2") (pinfunction "2_P$2") (pintype "passive"))
      (node (ref "U1") (pin "14") (pinfunction "VDDIO_14") (pintype "power_in"))
      (node (ref "U3") (pin "110") (pinfunction "VCC(IO)5_110") (pintype "bidirectional"))
      (node (ref "U3") (pin "123") (pinfunction "VCC(IO)6_123") (pintype "bidirectional"))
      (node (ref "U3") (pin "138") (pinfunction "VCC(IO)7_138") (pintype "bidirectional"))
      (node (ref "U3") (pin "149") (pinfunction "VCC(IO)8_149") (pintype "bidirectional"))
      (node (ref "U3") (pin "154") (pinfunction "VREFH_154") (pintype "bidirectional"))
      (node (ref "U3") (pin "155") (pinfunction "AVCC0_155") (pintype "bidirectional"))
      (node (ref "U3") (pin "158") (pinfunction "VREFH0_158") (pintype "bidirectional"))
      (node (ref "U3") (pin "171") (pinfunction "VCC(IO)9_171") (pintype "bidirectional"))
      (node (ref "U3") (pin "25") (pinfunction "VCC1_25") (pintype "bidirectional"))
      (node (ref "U3") (pin "26") (pinfunction "AVCC_SUBHS_26") (pintype "bidirectional"))
      (node (ref "U3") (pin "34") (pinfunction "VCC_USBHS_34") (pintype "bidirectional"))
      (node (ref "U3") (pin "48") (pinfunction "VCC_USB_48") (pintype "bidirectional"))
      (node (ref "U3") (pin "61") (pinfunction "VCC(IO)2_61") (pintype "bidirectional"))
      (node (ref "U3") (pin "84") (pinfunction "VCC(IO)3_84") (pintype "bidirectional"))
      (node (ref "U3") (pin "97") (pinfunction "VCC(IO)4_97") (pintype "bidirectional"))
    )
    (net (code "162") (name "VDD5") (class "Default")
      (node (ref "C23") (pin "P$1") (pinfunction "1_P$1") (pintype "passive"))
      (node (ref "C26") (pin "P$1") (pinfunction "1_P$1") (pintype "passive"))
      (node (ref "J2") (pin "P$3") (pinfunction "P$3_P$3") (pintype "bidirectional"))
      (node (ref "R19") (pin "P$2") (pinfunction "2_P$2") (pintype "passive"))
      (node (ref "R20") (pin "P$2") (pinfunction "2_P$2") (pintype "passive"))
      (node (ref "U2") (pin "4") (pinfunction "VIN_4") (pintype "input"))
    )
    (net (code "163") (name "VDDIN") (class "Default")
      (node (ref "J2") (pin "P$2") (pinfunction "P$2_P$2") (pintype "bidirectional"))
      (node (ref "L1") (pin "1") (pinfunction "P$1_1") (pintype "bidirectional"))
    )
    (net (code "164") (name "VDD_1.2") (class "Default")
      (node (ref "C10") (pin "P$1") (pinfunction "1_P$1") (pintype "passive"))
      (node (ref "C11") (pin "P$1") (pinfunction "1_P$1") (pintype "passive"))
      (node (ref "U1") (pin "1") (pinfunction "VDD_1.2_1") (pintype "power_in"))
    )
    (net (code "165") (name "XCIN") (class "Default")
      (node (ref "C32") (pin "P$1") (pinfunction "1_P$1") (pintype "passive"))
      (node (ref "U3") (pin "20") (pinfunction "XCIN_20") (pintype "bidirectional"))
      (node (ref "X3") (pin "P$1") (pinfunction "P$1_P$1") (pintype "bidirectional"))
    )
    (net (code "166") (name "XCOUT") (class "Default")
      (node (ref "C37") (pin "P$1") (pinfunction "1_P$1") (pintype "passive"))
      (node (ref "U3") (pin "21") (pinfunction "XCOUT_21") (pintype "bidirectional"))
      (node (ref "X3") (pin "P$2") (pinfunction "P$2_P$2") (pintype "bidirectional"))
    )
    (net (code "167") (name "XII") (class "Default")
      (node (ref "C1") (pin "P$1") (pinfunction "1_P$1") (pintype "passive"))
      (node (ref "U1") (pin "8") (pinfunction "XI_8") (pintype "input"))
      (node (ref "X1") (pin "1") (pinfunction "1_1") (pintype "bidirectional"))
    )
    (net (code "168") (name "XOO") (class "Default")
      (node (ref "C2") (pin "P$1") (pinfunction "1_P$1") (pintype "passive"))
      (node (ref "U1") (pin "7") (pinfunction "XO_7") (pintype "output"))
      (node (ref "X1") (pin "3") (pinfunction "3_3") (pintype "bidirectional"))
    )
    (net (code "169") (name "XTAL1") (class "Default")
      (node (ref "C17") (pin "P$1") (pinfunction "1_P$1") (pintype "passive"))
      (node (ref "U3") (pin "23") (pinfunction "P2_13/XTAL_23") (pintype "bidirectional"))
      (node (ref "X2") (pin "1") (pinfunction "1_1") (pintype "bidirectional"))
    )
    (net (code "170") (name "XTAL2") (class "Default")
      (node (ref "C18") (pin "P$1") (pinfunction "1_P$1") (pintype "passive"))
      (node (ref "U3") (pin "24") (pinfunction "P2_12/EXTAL_24") (pintype "bidirectional"))
      (node (ref "X2") (pin "3") (pinfunction "3_3") (pintype "bidirectional"))
    )
    (net (code "171") (name "unconnected-(U3-VBAT-Pad18)") (class "Default")
      (node (ref "U3") (pin "18") (pinfunction "VBAT_18") (pintype "bidirectional"))
    )
  )
)
